# AVALON_hashunit_chip.net
KiCad netlist of a schematic drawn in Altium Designer
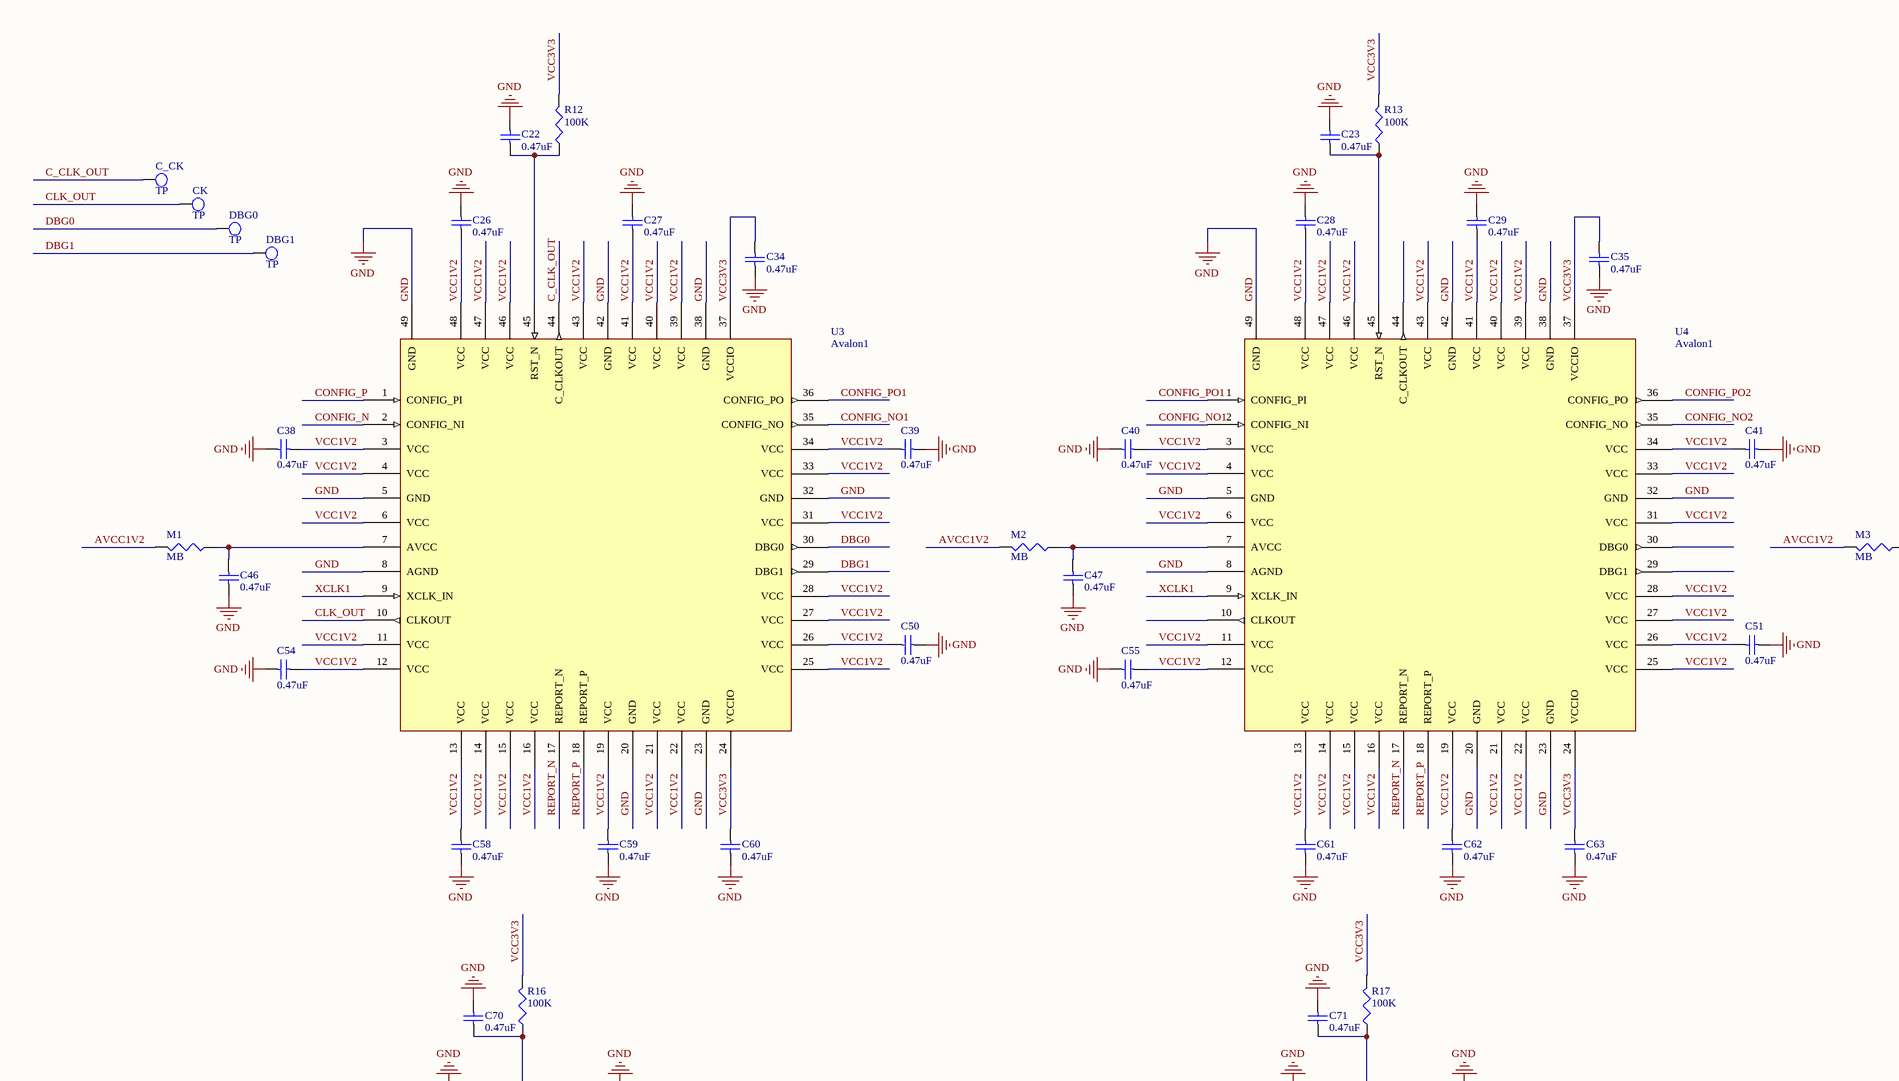
[diagram p0: AVALON_hashunit_chip.SchDoc, top left]
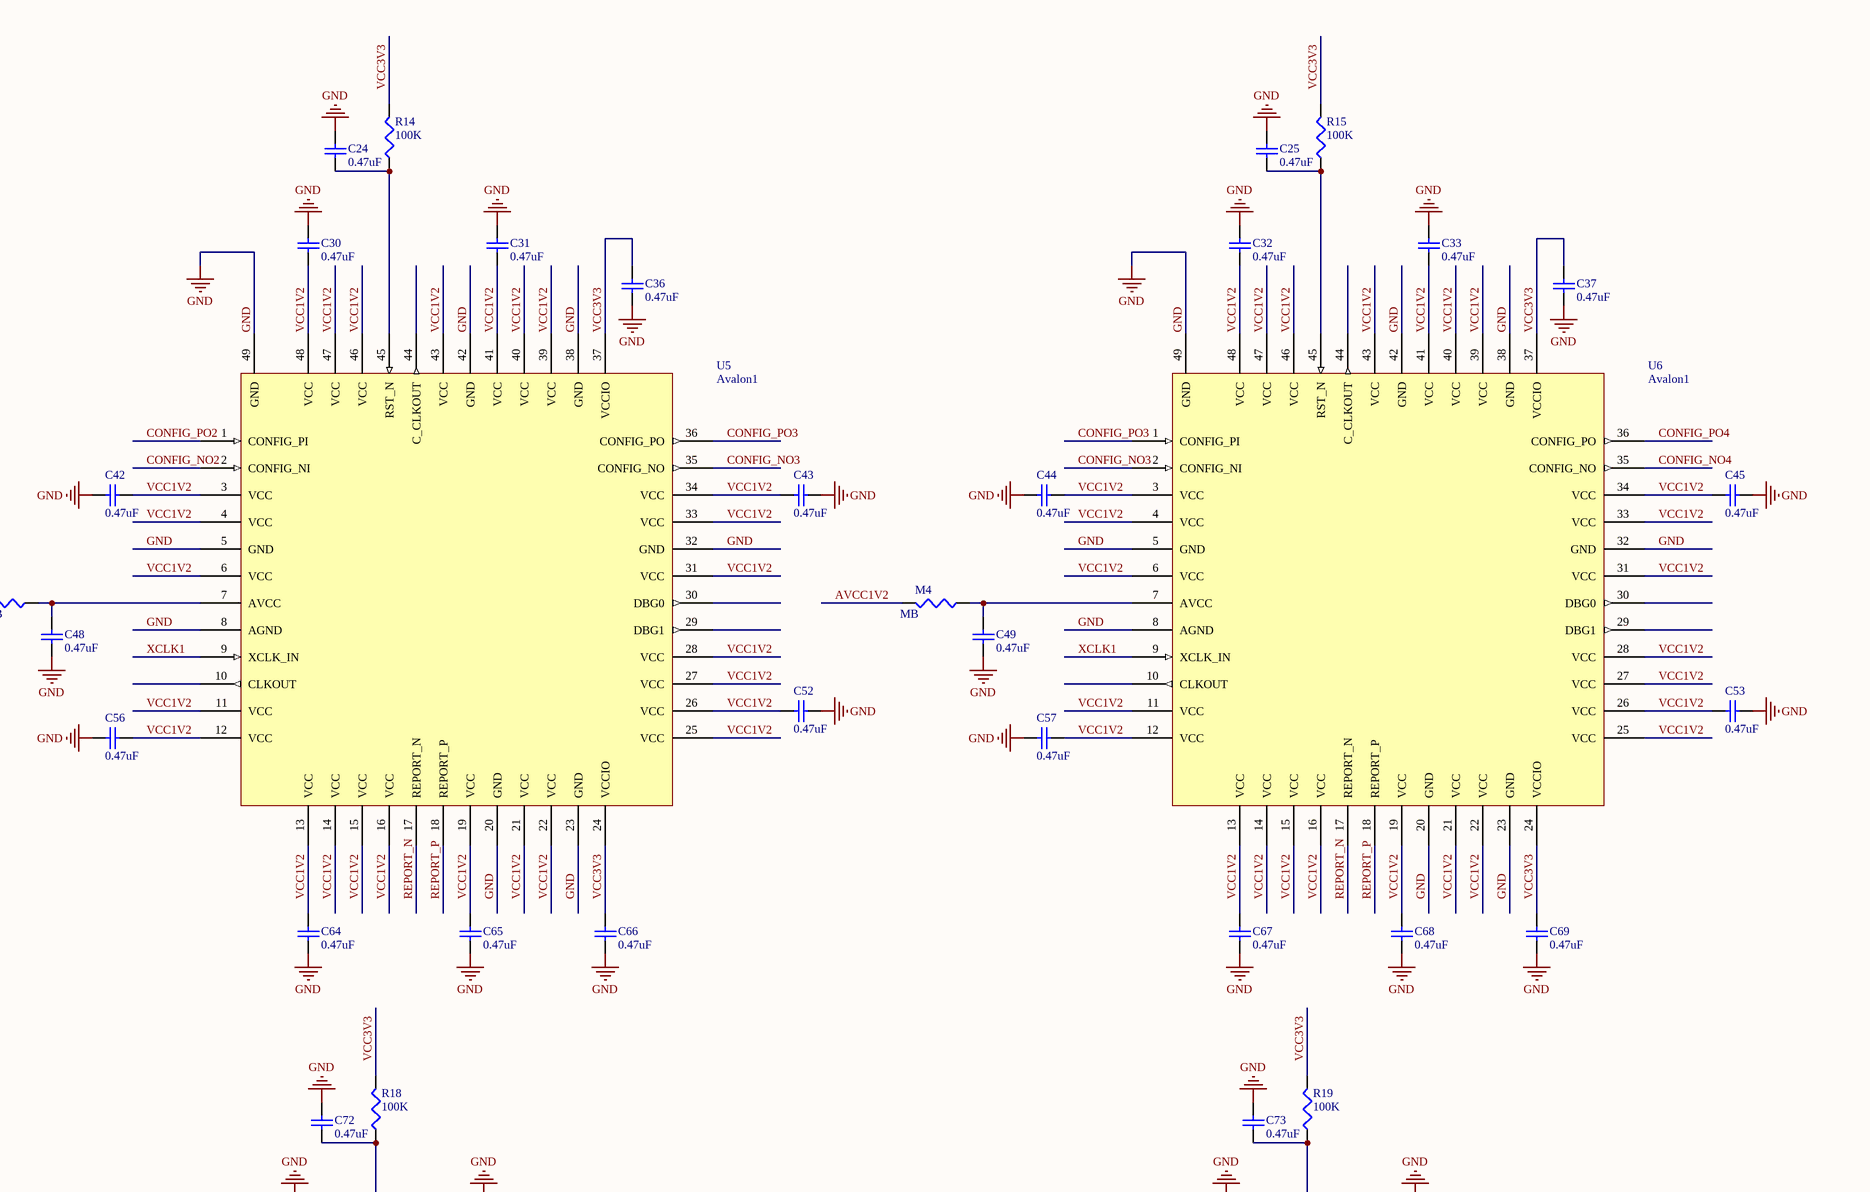
[diagram p1: AVALON_hashunit_chip.SchDoc, top right]
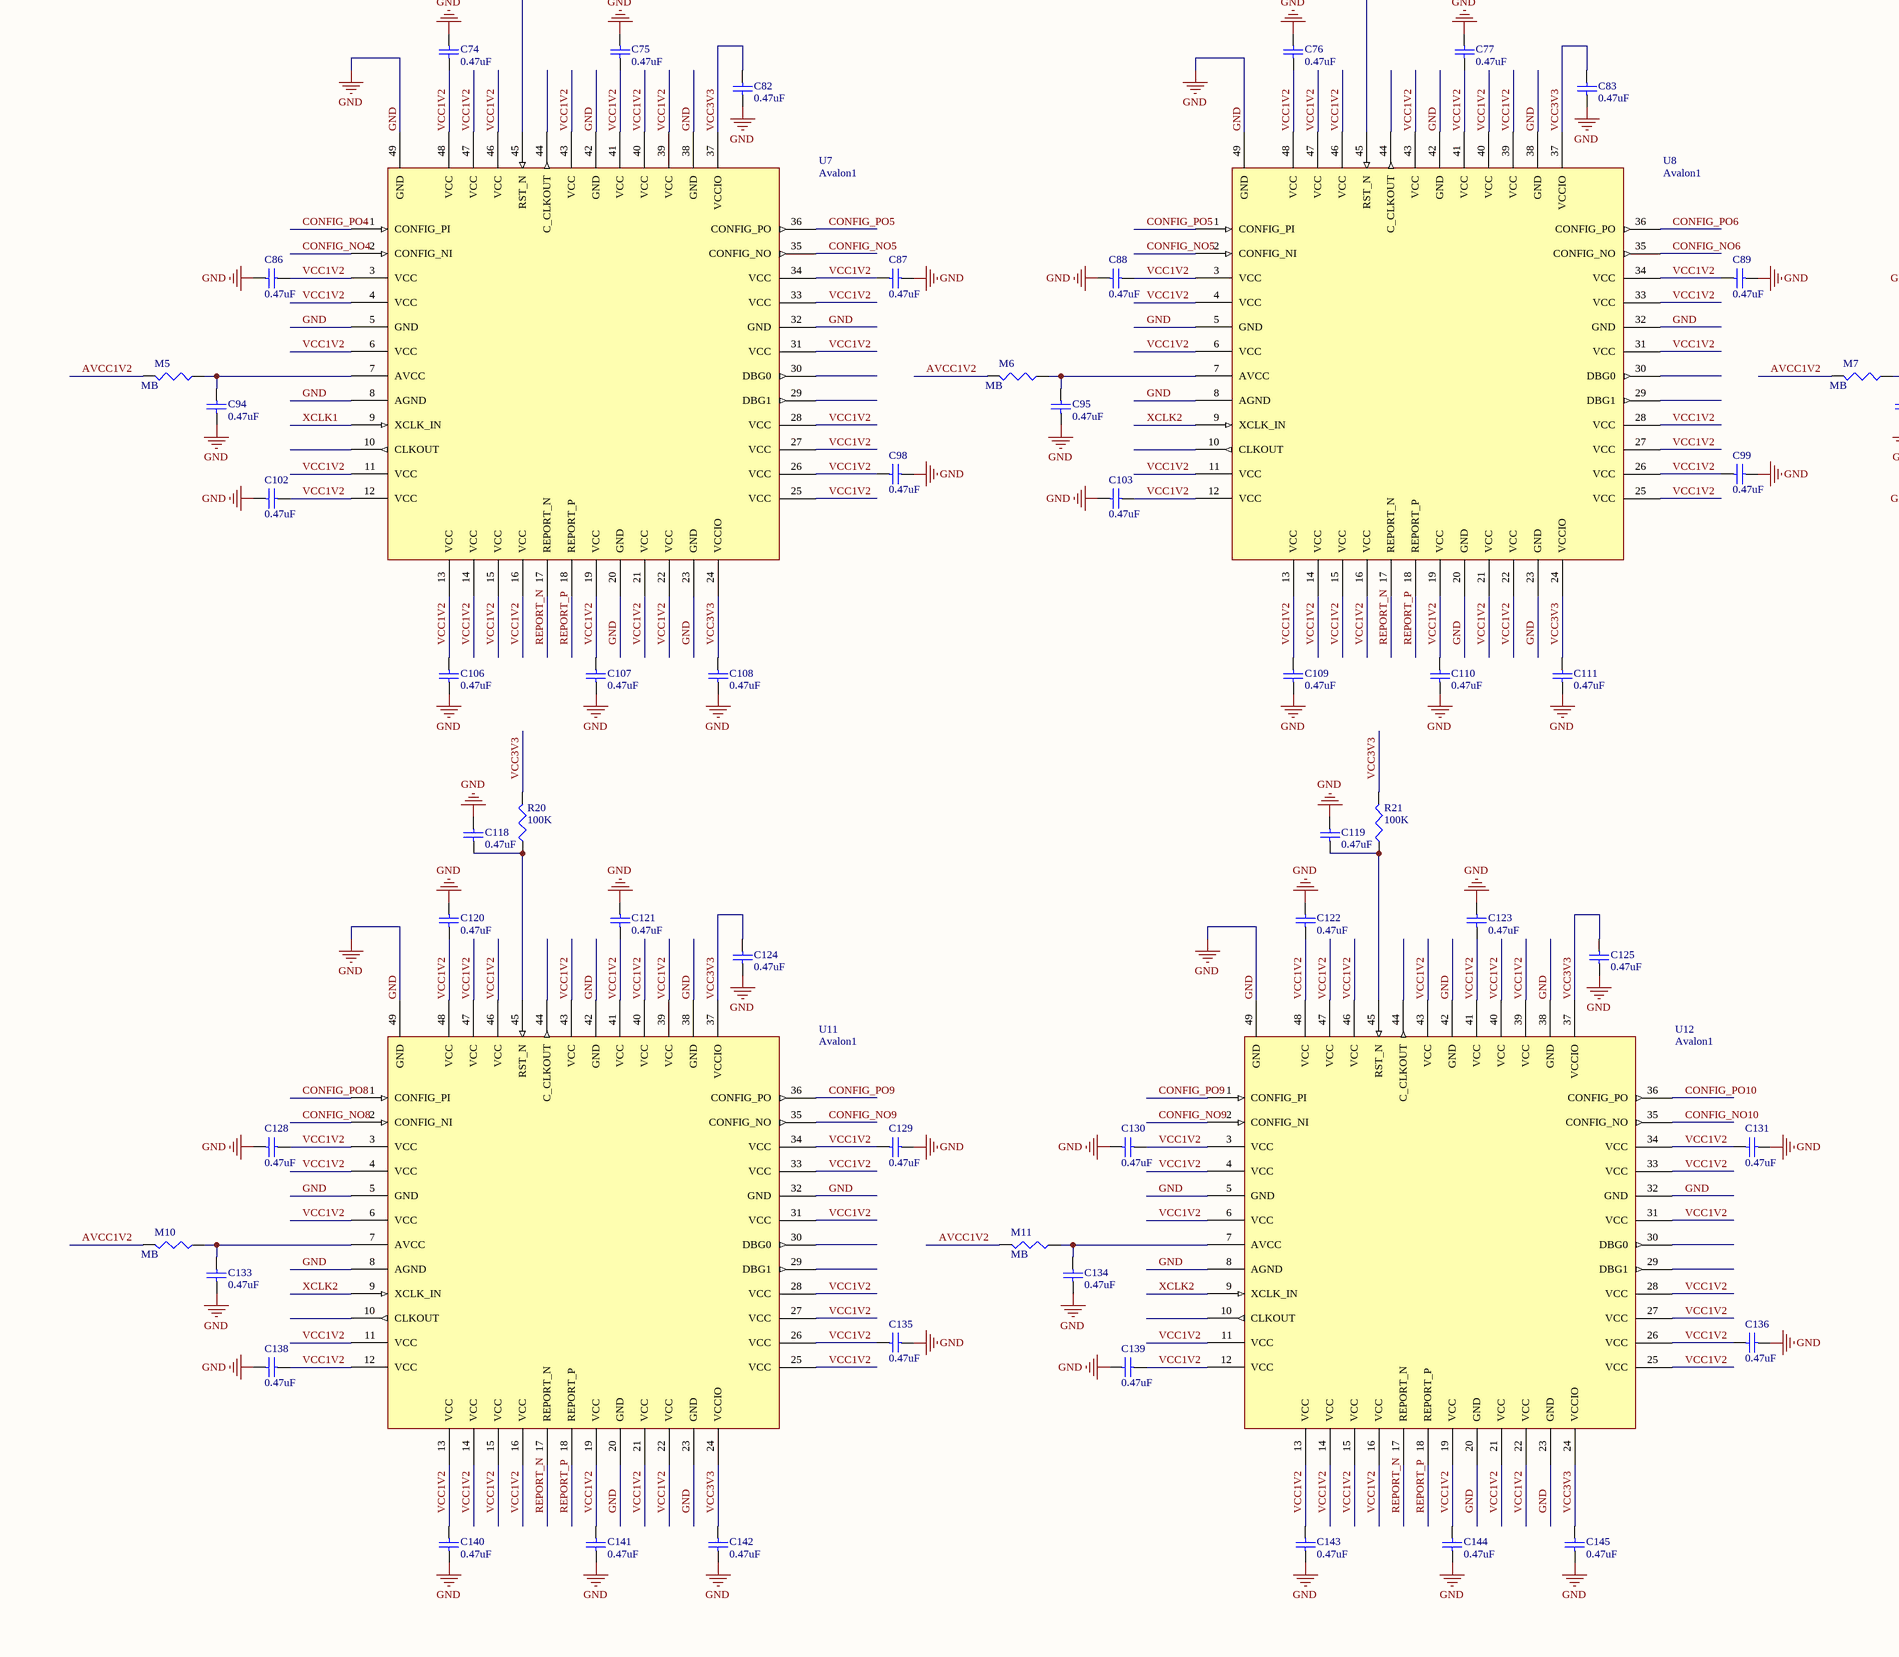
[diagram p2: AVALON_hashunit_chip.SchDoc, bottom left]
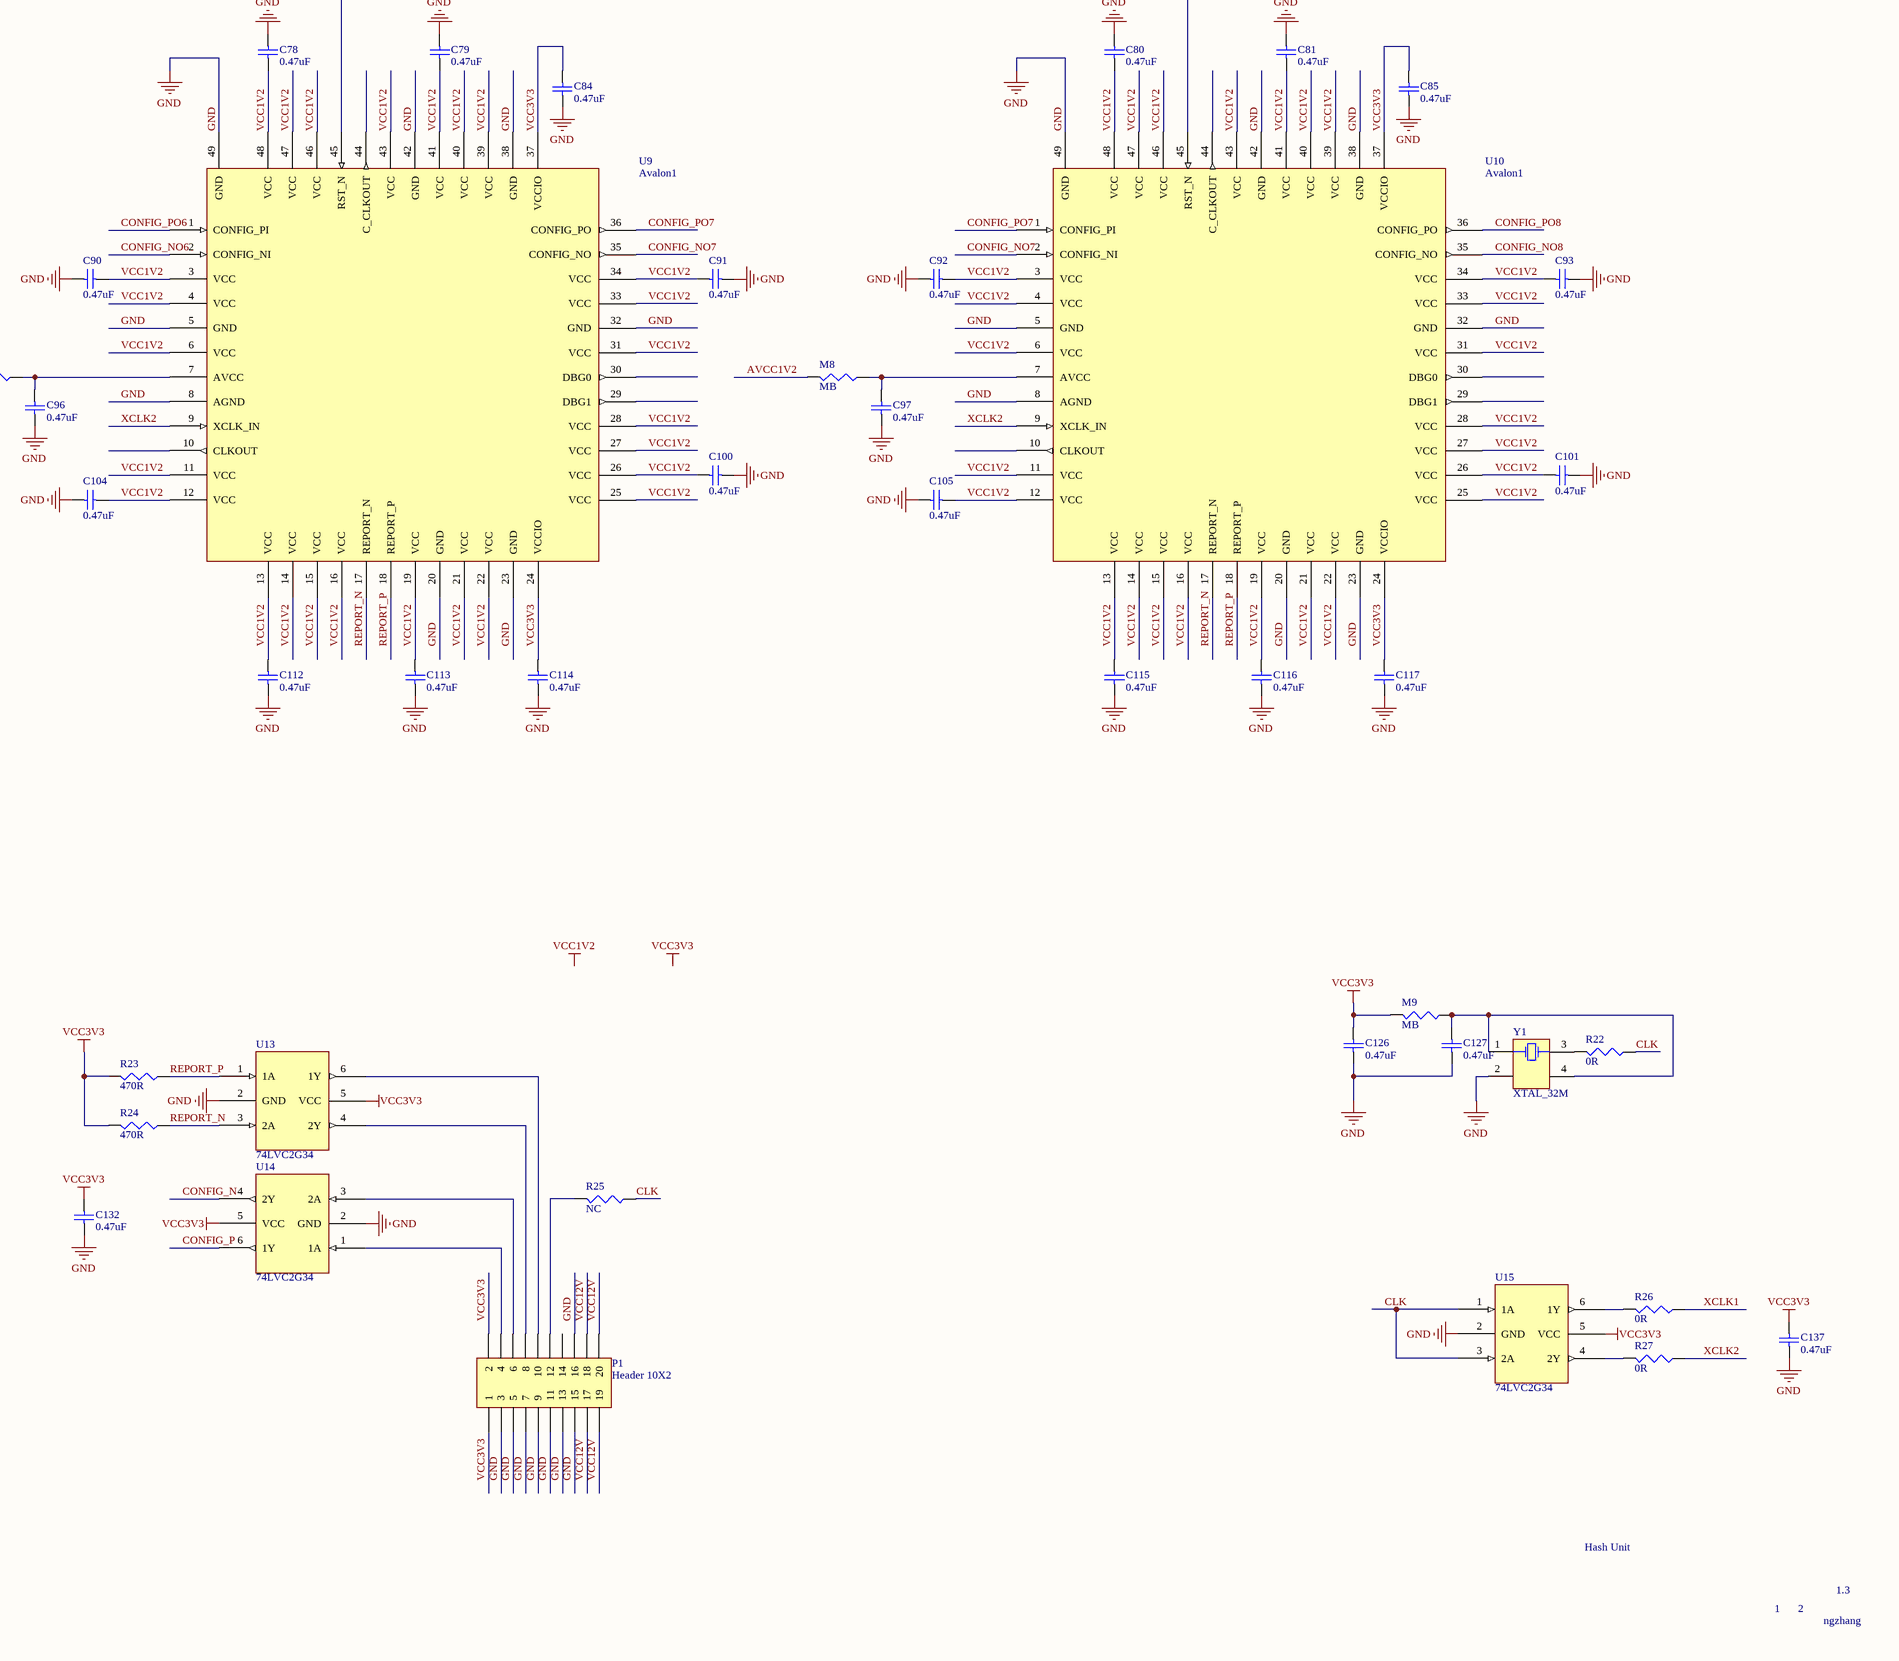
[diagram p3: AVALON_hashunit_chip.SchDoc, bottom right]

(export (version "E")
  (design (tool "Eeschema 10.0.6"))
  (components
    (comp (ref "C22")
      (value "0.47uF")
      (footprint "CAPC1005L")
      (description "Capacitor (Semiconductor SIM Model)")
      (fields (field (name "PUBLISHER") "Altium Limited"))
      (libsource (lib "Miscellaneous Devices") (part "Cap Semi"))
    )
    (comp (ref "C23")
      (value "0.47uF")
      (footprint "CAPC1005L")
      (description "Capacitor (Semiconductor SIM Model)")
      (fields (field (name "PUBLISHER") "Altium Limited"))
      (libsource (lib "Miscellaneous Devices") (part "Cap Semi"))
    )
    (comp (ref "C24")
      (value "0.47uF")
      (footprint "CAPC1005L")
      (description "Capacitor (Semiconductor SIM Model)")
      (fields (field (name "PUBLISHER") "Altium Limited"))
      (libsource (lib "Miscellaneous Devices") (part "Cap Semi"))
    )
    (comp (ref "C25")
      (value "0.47uF")
      (footprint "CAPC1005L")
      (description "Capacitor (Semiconductor SIM Model)")
      (fields (field (name "PUBLISHER") "Altium Limited"))
      (libsource (lib "Miscellaneous Devices") (part "Cap Semi"))
    )
    (comp (ref "C26")
      (value "0.47uF")
      (footprint "CAPC1005L")
      (description "Capacitor (Semiconductor SIM Model)")
      (fields (field (name "PUBLISHER") "Altium Limited"))
      (libsource (lib "Miscellaneous Devices") (part "Cap Semi"))
    )
    (comp (ref "C27")
      (value "0.47uF")
      (footprint "CAPC1005L")
      (description "Capacitor (Semiconductor SIM Model)")
      (fields (field (name "PUBLISHER") "Altium Limited"))
      (libsource (lib "Miscellaneous Devices") (part "Cap Semi"))
    )
    (comp (ref "C28")
      (value "0.47uF")
      (footprint "CAPC1005L")
      (description "Capacitor (Semiconductor SIM Model)")
      (fields (field (name "PUBLISHER") "Altium Limited"))
      (libsource (lib "Miscellaneous Devices") (part "Cap Semi"))
    )
    (comp (ref "C29")
      (value "0.47uF")
      (footprint "CAPC1005L")
      (description "Capacitor (Semiconductor SIM Model)")
      (fields (field (name "PUBLISHER") "Altium Limited"))
      (libsource (lib "Miscellaneous Devices") (part "Cap Semi"))
    )
    (comp (ref "C30")
      (value "0.47uF")
      (footprint "CAPC1005L")
      (description "Capacitor (Semiconductor SIM Model)")
      (fields (field (name "PUBLISHER") "Altium Limited"))
      (libsource (lib "Miscellaneous Devices") (part "Cap Semi"))
    )
    (comp (ref "C31")
      (value "0.47uF")
      (footprint "CAPC1005L")
      (description "Capacitor (Semiconductor SIM Model)")
      (fields (field (name "PUBLISHER") "Altium Limited"))
      (libsource (lib "Miscellaneous Devices") (part "Cap Semi"))
    )
    (comp (ref "C32")
      (value "0.47uF")
      (footprint "CAPC1005L")
      (description "Capacitor (Semiconductor SIM Model)")
      (fields (field (name "PUBLISHER") "Altium Limited"))
      (libsource (lib "Miscellaneous Devices") (part "Cap Semi"))
    )
    (comp (ref "C33")
      (value "0.47uF")
      (footprint "CAPC1005L")
      (description "Capacitor (Semiconductor SIM Model)")
      (fields (field (name "PUBLISHER") "Altium Limited"))
      (libsource (lib "Miscellaneous Devices") (part "Cap Semi"))
    )
    (comp (ref "C34")
      (value "0.47uF")
      (footprint "CAPC1005L")
      (description "Capacitor (Semiconductor SIM Model)")
      (fields (field (name "PUBLISHER") "Altium Limited"))
      (libsource (lib "Miscellaneous Devices") (part "Cap Semi"))
    )
    (comp (ref "C35")
      (value "0.47uF")
      (footprint "CAPC1005L")
      (description "Capacitor (Semiconductor SIM Model)")
      (fields (field (name "PUBLISHER") "Altium Limited"))
      (libsource (lib "Miscellaneous Devices") (part "Cap Semi"))
    )
    (comp (ref "C36")
      (value "0.47uF")
      (footprint "CAPC1005L")
      (description "Capacitor (Semiconductor SIM Model)")
      (fields (field (name "PUBLISHER") "Altium Limited"))
      (libsource (lib "Miscellaneous Devices") (part "Cap Semi"))
    )
    (comp (ref "C37")
      (value "0.47uF")
      (footprint "CAPC1005L")
      (description "Capacitor (Semiconductor SIM Model)")
      (fields (field (name "PUBLISHER") "Altium Limited"))
      (libsource (lib "Miscellaneous Devices") (part "Cap Semi"))
    )
    (comp (ref "C38")
      (value "0.47uF")
      (footprint "CAPC1005L")
      (description "Capacitor (Semiconductor SIM Model)")
      (fields (field (name "PUBLISHER") "Altium Limited"))
      (libsource (lib "Miscellaneous Devices") (part "Cap Semi"))
    )
    (comp (ref "C39")
      (value "0.47uF")
      (footprint "CAPC1005L")
      (description "Capacitor (Semiconductor SIM Model)")
      (fields (field (name "PUBLISHER") "Altium Limited"))
      (libsource (lib "Miscellaneous Devices") (part "Cap Semi"))
    )
    (comp (ref "C40")
      (value "0.47uF")
      (footprint "CAPC1005L")
      (description "Capacitor (Semiconductor SIM Model)")
      (fields (field (name "PUBLISHER") "Altium Limited"))
      (libsource (lib "Miscellaneous Devices") (part "Cap Semi"))
    )
    (comp (ref "C41")
      (value "0.47uF")
      (footprint "CAPC1005L")
      (description "Capacitor (Semiconductor SIM Model)")
      (fields (field (name "PUBLISHER") "Altium Limited"))
      (libsource (lib "Miscellaneous Devices") (part "Cap Semi"))
    )
    (comp (ref "C42")
      (value "0.47uF")
      (footprint "CAPC1005L")
      (description "Capacitor (Semiconductor SIM Model)")
      (fields (field (name "PUBLISHER") "Altium Limited"))
      (libsource (lib "Miscellaneous Devices") (part "Cap Semi"))
    )
    (comp (ref "C43")
      (value "0.47uF")
      (footprint "CAPC1005L")
      (description "Capacitor (Semiconductor SIM Model)")
      (fields (field (name "PUBLISHER") "Altium Limited"))
      (libsource (lib "Miscellaneous Devices") (part "Cap Semi"))
    )
    (comp (ref "C44")
      (value "0.47uF")
      (footprint "CAPC1005L")
      (description "Capacitor (Semiconductor SIM Model)")
      (fields (field (name "PUBLISHER") "Altium Limited"))
      (libsource (lib "Miscellaneous Devices") (part "Cap Semi"))
    )
    (comp (ref "C45")
      (value "0.47uF")
      (footprint "CAPC1005L")
      (description "Capacitor (Semiconductor SIM Model)")
      (fields (field (name "PUBLISHER") "Altium Limited"))
      (libsource (lib "Miscellaneous Devices") (part "Cap Semi"))
    )
    (comp (ref "C46")
      (value "0.47uF")
      (footprint "CAPC1005L")
      (description "Capacitor (Semiconductor SIM Model)")
      (fields (field (name "PUBLISHER") "Altium Limited"))
      (libsource (lib "Miscellaneous Devices") (part "Cap Semi"))
    )
    (comp (ref "C47")
      (value "0.47uF")
      (footprint "CAPC1005L")
      (description "Capacitor (Semiconductor SIM Model)")
      (fields (field (name "PUBLISHER") "Altium Limited"))
      (libsource (lib "Miscellaneous Devices") (part "Cap Semi"))
    )
    (comp (ref "C48")
      (value "0.47uF")
      (footprint "CAPC1005L")
      (description "Capacitor (Semiconductor SIM Model)")
      (fields (field (name "PUBLISHER") "Altium Limited"))
      (libsource (lib "Miscellaneous Devices") (part "Cap Semi"))
    )
    (comp (ref "C49")
      (value "0.47uF")
      (footprint "CAPC1005L")
      (description "Capacitor (Semiconductor SIM Model)")
      (fields (field (name "PUBLISHER") "Altium Limited"))
      (libsource (lib "Miscellaneous Devices") (part "Cap Semi"))
    )
    (comp (ref "C50")
      (value "0.47uF")
      (footprint "CAPC1005L")
      (description "Capacitor (Semiconductor SIM Model)")
      (fields (field (name "PUBLISHER") "Altium Limited"))
      (libsource (lib "Miscellaneous Devices") (part "Cap Semi"))
    )
    (comp (ref "C51")
      (value "0.47uF")
      (footprint "CAPC1005L")
      (description "Capacitor (Semiconductor SIM Model)")
      (fields (field (name "PUBLISHER") "Altium Limited"))
      (libsource (lib "Miscellaneous Devices") (part "Cap Semi"))
    )
    (comp (ref "C52")
      (value "0.47uF")
      (footprint "CAPC1005L")
      (description "Capacitor (Semiconductor SIM Model)")
      (fields (field (name "PUBLISHER") "Altium Limited"))
      (libsource (lib "Miscellaneous Devices") (part "Cap Semi"))
    )
    (comp (ref "C53")
      (value "0.47uF")
      (footprint "CAPC1005L")
      (description "Capacitor (Semiconductor SIM Model)")
      (fields (field (name "PUBLISHER") "Altium Limited"))
      (libsource (lib "Miscellaneous Devices") (part "Cap Semi"))
    )
    (comp (ref "C54")
      (value "0.47uF")
      (footprint "CAPC1005L")
      (description "Capacitor (Semiconductor SIM Model)")
      (fields (field (name "PUBLISHER") "Altium Limited"))
      (libsource (lib "Miscellaneous Devices") (part "Cap Semi"))
    )
    (comp (ref "C55")
      (value "0.47uF")
      (footprint "CAPC1005L")
      (description "Capacitor (Semiconductor SIM Model)")
      (fields (field (name "PUBLISHER") "Altium Limited"))
      (libsource (lib "Miscellaneous Devices") (part "Cap Semi"))
    )
    (comp (ref "C56")
      (value "0.47uF")
      (footprint "CAPC1005L")
      (description "Capacitor (Semiconductor SIM Model)")
      (fields (field (name "PUBLISHER") "Altium Limited"))
      (libsource (lib "Miscellaneous Devices") (part "Cap Semi"))
    )
    (comp (ref "C57")
      (value "0.47uF")
      (footprint "CAPC1005L")
      (description "Capacitor (Semiconductor SIM Model)")
      (fields (field (name "PUBLISHER") "Altium Limited"))
      (libsource (lib "Miscellaneous Devices") (part "Cap Semi"))
    )
    (comp (ref "C58")
      (value "0.47uF")
      (footprint "CAPC1005L")
      (description "Capacitor (Semiconductor SIM Model)")
      (fields (field (name "PUBLISHER") "Altium Limited"))
      (libsource (lib "Miscellaneous Devices") (part "Cap Semi"))
    )
    (comp (ref "C59")
      (value "0.47uF")
      (footprint "CAPC1005L")
      (description "Capacitor (Semiconductor SIM Model)")
      (fields (field (name "PUBLISHER") "Altium Limited"))
      (libsource (lib "Miscellaneous Devices") (part "Cap Semi"))
    )
    (comp (ref "C60")
      (value "0.47uF")
      (footprint "CAPC1005L")
      (description "Capacitor (Semiconductor SIM Model)")
      (fields (field (name "PUBLISHER") "Altium Limited"))
      (libsource (lib "Miscellaneous Devices") (part "Cap Semi"))
    )
    (comp (ref "C61")
      (value "0.47uF")
      (footprint "CAPC1005L")
      (description "Capacitor (Semiconductor SIM Model)")
      (fields (field (name "PUBLISHER") "Altium Limited"))
      (libsource (lib "Miscellaneous Devices") (part "Cap Semi"))
    )
    (comp (ref "C62")
      (value "0.47uF")
      (footprint "CAPC1005L")
      (description "Capacitor (Semiconductor SIM Model)")
      (fields (field (name "PUBLISHER") "Altium Limited"))
      (libsource (lib "Miscellaneous Devices") (part "Cap Semi"))
    )
    (comp (ref "C63")
      (value "0.47uF")
      (footprint "CAPC1005L")
      (description "Capacitor (Semiconductor SIM Model)")
      (fields (field (name "PUBLISHER") "Altium Limited"))
      (libsource (lib "Miscellaneous Devices") (part "Cap Semi"))
    )
    (comp (ref "C64")
      (value "0.47uF")
      (footprint "CAPC1005L")
      (description "Capacitor (Semiconductor SIM Model)")
      (fields (field (name "PUBLISHER") "Altium Limited"))
      (libsource (lib "Miscellaneous Devices") (part "Cap Semi"))
    )
    (comp (ref "C65")
      (value "0.47uF")
      (footprint "CAPC1005L")
      (description "Capacitor (Semiconductor SIM Model)")
      (fields (field (name "PUBLISHER") "Altium Limited"))
      (libsource (lib "Miscellaneous Devices") (part "Cap Semi"))
    )
    (comp (ref "C66")
      (value "0.47uF")
      (footprint "CAPC1005L")
      (description "Capacitor (Semiconductor SIM Model)")
      (fields (field (name "PUBLISHER") "Altium Limited"))
      (libsource (lib "Miscellaneous Devices") (part "Cap Semi"))
    )
    (comp (ref "C67")
      (value "0.47uF")
      (footprint "CAPC1005L")
      (description "Capacitor (Semiconductor SIM Model)")
      (fields (field (name "PUBLISHER") "Altium Limited"))
      (libsource (lib "Miscellaneous Devices") (part "Cap Semi"))
    )
    (comp (ref "C68")
      (value "0.47uF")
      (footprint "CAPC1005L")
      (description "Capacitor (Semiconductor SIM Model)")
      (fields (field (name "PUBLISHER") "Altium Limited"))
      (libsource (lib "Miscellaneous Devices") (part "Cap Semi"))
    )
    (comp (ref "C69")
      (value "0.47uF")
      (footprint "CAPC1005L")
      (description "Capacitor (Semiconductor SIM Model)")
      (fields (field (name "PUBLISHER") "Altium Limited"))
      (libsource (lib "Miscellaneous Devices") (part "Cap Semi"))
    )
    (comp (ref "C70")
      (value "0.47uF")
      (footprint "CAPC1005L")
      (description "Capacitor (Semiconductor SIM Model)")
      (fields (field (name "PUBLISHER") "Altium Limited"))
      (libsource (lib "Miscellaneous Devices") (part "Cap Semi"))
    )
    (comp (ref "C71")
      (value "0.47uF")
      (footprint "CAPC1005L")
      (description "Capacitor (Semiconductor SIM Model)")
      (fields (field (name "PUBLISHER") "Altium Limited"))
      (libsource (lib "Miscellaneous Devices") (part "Cap Semi"))
    )
    (comp (ref "C72")
      (value "0.47uF")
      (footprint "CAPC1005L")
      (description "Capacitor (Semiconductor SIM Model)")
      (fields (field (name "PUBLISHER") "Altium Limited"))
      (libsource (lib "Miscellaneous Devices") (part "Cap Semi"))
    )
    (comp (ref "C73")
      (value "0.47uF")
      (footprint "CAPC1005L")
      (description "Capacitor (Semiconductor SIM Model)")
      (fields (field (name "PUBLISHER") "Altium Limited"))
      (libsource (lib "Miscellaneous Devices") (part "Cap Semi"))
    )
    (comp (ref "C74")
      (value "0.47uF")
      (footprint "CAPC1005L")
      (description "Capacitor (Semiconductor SIM Model)")
      (fields (field (name "PUBLISHER") "Altium Limited"))
      (libsource (lib "Miscellaneous Devices") (part "Cap Semi"))
    )
    (comp (ref "C75")
      (value "0.47uF")
      (footprint "CAPC1005L")
      (description "Capacitor (Semiconductor SIM Model)")
      (fields (field (name "PUBLISHER") "Altium Limited"))
      (libsource (lib "Miscellaneous Devices") (part "Cap Semi"))
    )
    (comp (ref "C76")
      (value "0.47uF")
      (footprint "CAPC1005L")
      (description "Capacitor (Semiconductor SIM Model)")
      (fields (field (name "PUBLISHER") "Altium Limited"))
      (libsource (lib "Miscellaneous Devices") (part "Cap Semi"))
    )
    (comp (ref "C77")
      (value "0.47uF")
      (footprint "CAPC1005L")
      (description "Capacitor (Semiconductor SIM Model)")
      (fields (field (name "PUBLISHER") "Altium Limited"))
      (libsource (lib "Miscellaneous Devices") (part "Cap Semi"))
    )
    (comp (ref "C78")
      (value "0.47uF")
      (footprint "CAPC1005L")
      (description "Capacitor (Semiconductor SIM Model)")
      (fields (field (name "PUBLISHER") "Altium Limited"))
      (libsource (lib "Miscellaneous Devices") (part "Cap Semi"))
    )
    (comp (ref "C79")
      (value "0.47uF")
      (footprint "CAPC1005L")
      (description "Capacitor (Semiconductor SIM Model)")
      (fields (field (name "PUBLISHER") "Altium Limited"))
      (libsource (lib "Miscellaneous Devices") (part "Cap Semi"))
    )
    (comp (ref "C80")
      (value "0.47uF")
      (footprint "CAPC1005L")
      (description "Capacitor (Semiconductor SIM Model)")
      (fields (field (name "PUBLISHER") "Altium Limited"))
      (libsource (lib "Miscellaneous Devices") (part "Cap Semi"))
    )
    (comp (ref "C81")
      (value "0.47uF")
      (footprint "CAPC1005L")
      (description "Capacitor (Semiconductor SIM Model)")
      (fields (field (name "PUBLISHER") "Altium Limited"))
      (libsource (lib "Miscellaneous Devices") (part "Cap Semi"))
    )
    (comp (ref "C82")
      (value "0.47uF")
      (footprint "CAPC1005L")
      (description "Capacitor (Semiconductor SIM Model)")
      (fields (field (name "PUBLISHER") "Altium Limited"))
      (libsource (lib "Miscellaneous Devices") (part "Cap Semi"))
    )
    (comp (ref "C83")
      (value "0.47uF")
      (footprint "CAPC1005L")
      (description "Capacitor (Semiconductor SIM Model)")
      (fields (field (name "PUBLISHER") "Altium Limited"))
      (libsource (lib "Miscellaneous Devices") (part "Cap Semi"))
    )
    (comp (ref "C84")
      (value "0.47uF")
      (footprint "CAPC1005L")
      (description "Capacitor (Semiconductor SIM Model)")
      (fields (field (name "PUBLISHER") "Altium Limited"))
      (libsource (lib "Miscellaneous Devices") (part "Cap Semi"))
    )
    (comp (ref "C85")
      (value "0.47uF")
      (footprint "CAPC1005L")
      (description "Capacitor (Semiconductor SIM Model)")
      (fields (field (name "PUBLISHER") "Altium Limited"))
      (libsource (lib "Miscellaneous Devices") (part "Cap Semi"))
    )
    (comp (ref "C86")
      (value "0.47uF")
      (footprint "CAPC1005L")
      (description "Capacitor (Semiconductor SIM Model)")
      (fields (field (name "PUBLISHER") "Altium Limited"))
      (libsource (lib "Miscellaneous Devices") (part "Cap Semi"))
    )
    (comp (ref "C87")
      (value "0.47uF")
      (footprint "CAPC1005L")
      (description "Capacitor (Semiconductor SIM Model)")
      (fields (field (name "PUBLISHER") "Altium Limited"))
      (libsource (lib "Miscellaneous Devices") (part "Cap Semi"))
    )
    (comp (ref "C88")
      (value "0.47uF")
      (footprint "CAPC1005L")
      (description "Capacitor (Semiconductor SIM Model)")
      (fields (field (name "PUBLISHER") "Altium Limited"))
      (libsource (lib "Miscellaneous Devices") (part "Cap Semi"))
    )
    (comp (ref "C89")
      (value "0.47uF")
      (footprint "CAPC1005L")
      (description "Capacitor (Semiconductor SIM Model)")
      (fields (field (name "PUBLISHER") "Altium Limited"))
      (libsource (lib "Miscellaneous Devices") (part "Cap Semi"))
    )
    (comp (ref "C90")
      (value "0.47uF")
      (footprint "CAPC1005L")
      (description "Capacitor (Semiconductor SIM Model)")
      (fields (field (name "PUBLISHER") "Altium Limited"))
      (libsource (lib "Miscellaneous Devices") (part "Cap Semi"))
    )
    (comp (ref "C91")
      (value "0.47uF")
      (footprint "CAPC1005L")
      (description "Capacitor (Semiconductor SIM Model)")
      (fields (field (name "PUBLISHER") "Altium Limited"))
      (libsource (lib "Miscellaneous Devices") (part "Cap Semi"))
    )
    (comp (ref "C92")
      (value "0.47uF")
      (footprint "CAPC1005L")
      (description "Capacitor (Semiconductor SIM Model)")
      (fields (field (name "PUBLISHER") "Altium Limited"))
      (libsource (lib "Miscellaneous Devices") (part "Cap Semi"))
    )
    (comp (ref "C93")
      (value "0.47uF")
      (footprint "CAPC1005L")
      (description "Capacitor (Semiconductor SIM Model)")
      (fields (field (name "PUBLISHER") "Altium Limited"))
      (libsource (lib "Miscellaneous Devices") (part "Cap Semi"))
    )
    (comp (ref "C94")
      (value "0.47uF")
      (footprint "CAPC1005L")
      (description "Capacitor (Semiconductor SIM Model)")
      (fields (field (name "PUBLISHER") "Altium Limited"))
      (libsource (lib "Miscellaneous Devices") (part "Cap Semi"))
    )
    (comp (ref "C95")
      (value "0.47uF")
      (footprint "CAPC1005L")
      (description "Capacitor (Semiconductor SIM Model)")
      (fields (field (name "PUBLISHER") "Altium Limited"))
      (libsource (lib "Miscellaneous Devices") (part "Cap Semi"))
    )
    (comp (ref "C96")
      (value "0.47uF")
      (footprint "CAPC1005L")
      (description "Capacitor (Semiconductor SIM Model)")
      (fields (field (name "PUBLISHER") "Altium Limited"))
      (libsource (lib "Miscellaneous Devices") (part "Cap Semi"))
    )
    (comp (ref "C97")
      (value "0.47uF")
      (footprint "CAPC1005L")
      (description "Capacitor (Semiconductor SIM Model)")
      (fields (field (name "PUBLISHER") "Altium Limited"))
      (libsource (lib "Miscellaneous Devices") (part "Cap Semi"))
    )
    (comp (ref "C98")
      (value "0.47uF")
      (footprint "CAPC1005L")
      (description "Capacitor (Semiconductor SIM Model)")
      (fields (field (name "PUBLISHER") "Altium Limited"))
      (libsource (lib "Miscellaneous Devices") (part "Cap Semi"))
    )
    (comp (ref "C99")
      (value "0.47uF")
      (footprint "CAPC1005L")
      (description "Capacitor (Semiconductor SIM Model)")
      (fields (field (name "PUBLISHER") "Altium Limited"))
      (libsource (lib "Miscellaneous Devices") (part "Cap Semi"))
    )
    (comp (ref "C100")
      (value "0.47uF")
      (footprint "CAPC1005L")
      (description "Capacitor (Semiconductor SIM Model)")
      (fields (field (name "PUBLISHER") "Altium Limited"))
      (libsource (lib "Miscellaneous Devices") (part "Cap Semi"))
    )
    (comp (ref "C101")
      (value "0.47uF")
      (footprint "CAPC1005L")
      (description "Capacitor (Semiconductor SIM Model)")
      (fields (field (name "PUBLISHER") "Altium Limited"))
      (libsource (lib "Miscellaneous Devices") (part "Cap Semi"))
    )
    (comp (ref "C102")
      (value "0.47uF")
      (footprint "CAPC1005L")
      (description "Capacitor (Semiconductor SIM Model)")
      (fields (field (name "PUBLISHER") "Altium Limited"))
      (libsource (lib "Miscellaneous Devices") (part "Cap Semi"))
    )
    (comp (ref "C103")
      (value "0.47uF")
      (footprint "CAPC1005L")
      (description "Capacitor (Semiconductor SIM Model)")
      (fields (field (name "PUBLISHER") "Altium Limited"))
      (libsource (lib "Miscellaneous Devices") (part "Cap Semi"))
    )
    (comp (ref "C104")
      (value "0.47uF")
      (footprint "CAPC1005L")
      (description "Capacitor (Semiconductor SIM Model)")
      (fields (field (name "PUBLISHER") "Altium Limited"))
      (libsource (lib "Miscellaneous Devices") (part "Cap Semi"))
    )
    (comp (ref "C105")
      (value "0.47uF")
      (footprint "CAPC1005L")
      (description "Capacitor (Semiconductor SIM Model)")
      (fields (field (name "PUBLISHER") "Altium Limited"))
      (libsource (lib "Miscellaneous Devices") (part "Cap Semi"))
    )
    (comp (ref "C106")
      (value "0.47uF")
      (footprint "CAPC1005L")
      (description "Capacitor (Semiconductor SIM Model)")
      (fields (field (name "PUBLISHER") "Altium Limited"))
      (libsource (lib "Miscellaneous Devices") (part "Cap Semi"))
    )
    (comp (ref "C107")
      (value "0.47uF")
      (footprint "CAPC1005L")
      (description "Capacitor (Semiconductor SIM Model)")
      (fields (field (name "PUBLISHER") "Altium Limited"))
      (libsource (lib "Miscellaneous Devices") (part "Cap Semi"))
    )
    (comp (ref "C108")
      (value "0.47uF")
      (footprint "CAPC1005L")
      (description "Capacitor (Semiconductor SIM Model)")
      (fields (field (name "PUBLISHER") "Altium Limited"))
      (libsource (lib "Miscellaneous Devices") (part "Cap Semi"))
    )
    (comp (ref "C109")
      (value "0.47uF")
      (footprint "CAPC1005L")
      (description "Capacitor (Semiconductor SIM Model)")
      (fields (field (name "PUBLISHER") "Altium Limited"))
      (libsource (lib "Miscellaneous Devices") (part "Cap Semi"))
    )
    (comp (ref "C110")
      (value "0.47uF")
      (footprint "CAPC1005L")
      (description "Capacitor (Semiconductor SIM Model)")
      (fields (field (name "PUBLISHER") "Altium Limited"))
      (libsource (lib "Miscellaneous Devices") (part "Cap Semi"))
    )
    (comp (ref "C111")
      (value "0.47uF")
      (footprint "CAPC1005L")
      (description "Capacitor (Semiconductor SIM Model)")
      (fields (field (name "PUBLISHER") "Altium Limited"))
      (libsource (lib "Miscellaneous Devices") (part "Cap Semi"))
    )
    (comp (ref "C112")
      (value "0.47uF")
      (footprint "CAPC1005L")
      (description "Capacitor (Semiconductor SIM Model)")
      (fields (field (name "PUBLISHER") "Altium Limited"))
      (libsource (lib "Miscellaneous Devices") (part "Cap Semi"))
    )
    (comp (ref "C113")
      (value "0.47uF")
      (footprint "CAPC1005L")
      (description "Capacitor (Semiconductor SIM Model)")
      (fields (field (name "PUBLISHER") "Altium Limited"))
      (libsource (lib "Miscellaneous Devices") (part "Cap Semi"))
    )
    (comp (ref "C114")
      (value "0.47uF")
      (footprint "CAPC1005L")
      (description "Capacitor (Semiconductor SIM Model)")
      (fields (field (name "PUBLISHER") "Altium Limited"))
      (libsource (lib "Miscellaneous Devices") (part "Cap Semi"))
    )
    (comp (ref "C115")
      (value "0.47uF")
      (footprint "CAPC1005L")
      (description "Capacitor (Semiconductor SIM Model)")
      (fields (field (name "PUBLISHER") "Altium Limited"))
      (libsource (lib "Miscellaneous Devices") (part "Cap Semi"))
    )
    (comp (ref "C116")
      (value "0.47uF")
      (footprint "CAPC1005L")
      (description "Capacitor (Semiconductor SIM Model)")
      (fields (field (name "PUBLISHER") "Altium Limited"))
      (libsource (lib "Miscellaneous Devices") (part "Cap Semi"))
    )
    (comp (ref "C117")
      (value "0.47uF")
      (footprint "CAPC1005L")
      (description "Capacitor (Semiconductor SIM Model)")
      (fields (field (name "PUBLISHER") "Altium Limited"))
      (libsource (lib "Miscellaneous Devices") (part "Cap Semi"))
    )
    (comp (ref "C118")
      (value "0.47uF")
      (footprint "CAPC1005L")
      (description "Capacitor (Semiconductor SIM Model)")
      (fields (field (name "PUBLISHER") "Altium Limited"))
      (libsource (lib "Miscellaneous Devices") (part "Cap Semi"))
    )
    (comp (ref "C119")
      (value "0.47uF")
      (footprint "CAPC1005L")
      (description "Capacitor (Semiconductor SIM Model)")
      (fields (field (name "PUBLISHER") "Altium Limited"))
      (libsource (lib "Miscellaneous Devices") (part "Cap Semi"))
    )
    (comp (ref "C120")
      (value "0.47uF")
      (footprint "CAPC1005L")
      (description "Capacitor (Semiconductor SIM Model)")
      (fields (field (name "PUBLISHER") "Altium Limited"))
      (libsource (lib "Miscellaneous Devices") (part "Cap Semi"))
    )
    (comp (ref "C121")
      (value "0.47uF")
      (footprint "CAPC1005L")
      (description "Capacitor (Semiconductor SIM Model)")
      (fields (field (name "PUBLISHER") "Altium Limited"))
      (libsource (lib "Miscellaneous Devices") (part "Cap Semi"))
    )
    (comp (ref "C122")
      (value "0.47uF")
      (footprint "CAPC1005L")
      (description "Capacitor (Semiconductor SIM Model)")
      (fields (field (name "PUBLISHER") "Altium Limited"))
      (libsource (lib "Miscellaneous Devices") (part "Cap Semi"))
    )
    (comp (ref "C123")
      (value "0.47uF")
      (footprint "CAPC1005L")
      (description "Capacitor (Semiconductor SIM Model)")
      (fields (field (name "PUBLISHER") "Altium Limited"))
      (libsource (lib "Miscellaneous Devices") (part "Cap Semi"))
    )
    (comp (ref "C124")
      (value "0.47uF")
      (footprint "CAPC1005L")
      (description "Capacitor (Semiconductor SIM Model)")
      (fields (field (name "PUBLISHER") "Altium Limited"))
      (libsource (lib "Miscellaneous Devices") (part "Cap Semi"))
    )
    (comp (ref "C125")
      (value "0.47uF")
      (footprint "CAPC1005L")
      (description "Capacitor (Semiconductor SIM Model)")
      (fields (field (name "PUBLISHER") "Altium Limited"))
      (libsource (lib "Miscellaneous Devices") (part "Cap Semi"))
    )
    (comp (ref "C126")
      (value "0.47uF")
      (footprint "CAPC1005L")
      (description "Capacitor (Semiconductor SIM Model)")
      (fields (field (name "PUBLISHER") "Altium Limited"))
      (libsource (lib "Miscellaneous Devices") (part "Cap Semi"))
    )
    (comp (ref "C127")
      (value "0.47uF")
      (footprint "CAPC1005L")
      (description "Capacitor (Semiconductor SIM Model)")
      (fields (field (name "PUBLISHER") "Altium Limited"))
      (libsource (lib "Miscellaneous Devices") (part "Cap Semi"))
    )
    (comp (ref "C128")
      (value "0.47uF")
      (footprint "CAPC1005L")
      (description "Capacitor (Semiconductor SIM Model)")
      (fields (field (name "PUBLISHER") "Altium Limited"))
      (libsource (lib "Miscellaneous Devices") (part "Cap Semi"))
    )
    (comp (ref "C129")
      (value "0.47uF")
      (footprint "CAPC1005L")
      (description "Capacitor (Semiconductor SIM Model)")
      (fields (field (name "PUBLISHER") "Altium Limited"))
      (libsource (lib "Miscellaneous Devices") (part "Cap Semi"))
    )
    (comp (ref "C130")
      (value "0.47uF")
      (footprint "CAPC1005L")
      (description "Capacitor (Semiconductor SIM Model)")
      (fields (field (name "PUBLISHER") "Altium Limited"))
      (libsource (lib "Miscellaneous Devices") (part "Cap Semi"))
    )
    (comp (ref "C131")
      (value "0.47uF")
      (footprint "CAPC1005L")
      (description "Capacitor (Semiconductor SIM Model)")
      (fields (field (name "PUBLISHER") "Altium Limited"))
      (libsource (lib "Miscellaneous Devices") (part "Cap Semi"))
    )
    (comp (ref "C132")
      (value "0.47uF")
      (footprint "CAPC1005L")
      (description "Capacitor (Semiconductor SIM Model)")
      (fields (field (name "PUBLISHER") "Altium Limited"))
      (libsource (lib "Miscellaneous Devices") (part "Cap Semi"))
    )
    (comp (ref "C133")
      (value "0.47uF")
      (footprint "CAPC1005L")
      (description "Capacitor (Semiconductor SIM Model)")
      (fields (field (name "PUBLISHER") "Altium Limited"))
      (libsource (lib "Miscellaneous Devices") (part "Cap Semi"))
    )
    (comp (ref "C134")
      (value "0.47uF")
      (footprint "CAPC1005L")
      (description "Capacitor (Semiconductor SIM Model)")
      (fields (field (name "PUBLISHER") "Altium Limited"))
      (libsource (lib "Miscellaneous Devices") (part "Cap Semi"))
    )
    (comp (ref "C135")
      (value "0.47uF")
      (footprint "CAPC1005L")
      (description "Capacitor (Semiconductor SIM Model)")
      (fields (field (name "PUBLISHER") "Altium Limited"))
      (libsource (lib "Miscellaneous Devices") (part "Cap Semi"))
    )
    (comp (ref "C136")
      (value "0.47uF")
      (footprint "CAPC1005L")
      (description "Capacitor (Semiconductor SIM Model)")
      (fields (field (name "PUBLISHER") "Altium Limited"))
      (libsource (lib "Miscellaneous Devices") (part "Cap Semi"))
    )
    (comp (ref "C137")
      (value "0.47uF")
      (footprint "IPC-7352 Chip_Capacitor_L:CAPC1005L")
      (description "Capacitor (Semiconductor SIM Model)")
      (fields (field (name "PUBLISHER") "Altium Limited"))
      (libsource (lib "Miscellaneous Devices") (part "Cap Semi"))
    )
    (comp (ref "C138")
      (value "0.47uF")
      (footprint "CAPC1005L")
      (description "Capacitor (Semiconductor SIM Model)")
      (fields (field (name "PUBLISHER") "Altium Limited"))
      (libsource (lib "Miscellaneous Devices") (part "Cap Semi"))
    )
    (comp (ref "C139")
      (value "0.47uF")
      (footprint "CAPC1005L")
      (description "Capacitor (Semiconductor SIM Model)")
      (fields (field (name "PUBLISHER") "Altium Limited"))
      (libsource (lib "Miscellaneous Devices") (part "Cap Semi"))
    )
    (comp (ref "C140")
      (value "0.47uF")
      (footprint "CAPC1005L")
      (description "Capacitor (Semiconductor SIM Model)")
      (fields (field (name "PUBLISHER") "Altium Limited"))
      (libsource (lib "Miscellaneous Devices") (part "Cap Semi"))
    )
    (comp (ref "C141")
      (value "0.47uF")
      (footprint "CAPC1005L")
      (description "Capacitor (Semiconductor SIM Model)")
      (fields (field (name "PUBLISHER") "Altium Limited"))
      (libsource (lib "Miscellaneous Devices") (part "Cap Semi"))
    )
    (comp (ref "C142")
      (value "0.47uF")
      (footprint "CAPC1005L")
      (description "Capacitor (Semiconductor SIM Model)")
      (fields (field (name "PUBLISHER") "Altium Limited"))
      (libsource (lib "Miscellaneous Devices") (part "Cap Semi"))
    )
    (comp (ref "C143")
      (value "0.47uF")
      (footprint "CAPC1005L")
      (description "Capacitor (Semiconductor SIM Model)")
      (fields (field (name "PUBLISHER") "Altium Limited"))
      (libsource (lib "Miscellaneous Devices") (part "Cap Semi"))
    )
    (comp (ref "C144")
      (value "0.47uF")
      (footprint "CAPC1005L")
      (description "Capacitor (Semiconductor SIM Model)")
      (fields (field (name "PUBLISHER") "Altium Limited"))
      (libsource (lib "Miscellaneous Devices") (part "Cap Semi"))
    )
    (comp (ref "C145")
      (value "0.47uF")
      (footprint "CAPC1005L")
      (description "Capacitor (Semiconductor SIM Model)")
      (fields (field (name "PUBLISHER") "Altium Limited"))
      (libsource (lib "Miscellaneous Devices") (part "Cap Semi"))
    )
    (comp (ref "CK") (value "TP") (footprint "TP") (libsource (lib "S6") (part "TP")))
    (comp (ref "C_CK") (value "TP") (footprint "TP") (libsource (lib "S6") (part "TP")))
    (comp (ref "DBG0") (value "TP") (footprint "TP") (libsource (lib "S6") (part "TP")))
    (comp (ref "DBG1") (value "TP") (footprint "TP") (libsource (lib "S6") (part "TP")))
    (comp (ref "M1")
      (value "MB")
      (footprint "RESC1005L")
      (fields (field (name "PUBLISHER") "Altium Limited"))
      (libsource (lib "Miscellaneous Devices") (part "Res3"))
    )
    (comp (ref "M2")
      (value "MB")
      (footprint "RESC1005L")
      (fields (field (name "PUBLISHER") "Altium Limited"))
      (libsource (lib "Miscellaneous Devices") (part "Res3"))
    )
    (comp (ref "M3")
      (value "MB")
      (footprint "RESC1005L")
      (fields (field (name "PUBLISHER") "Altium Limited"))
      (libsource (lib "Miscellaneous Devices") (part "Res3"))
    )
    (comp (ref "M4")
      (value "MB")
      (footprint "RESC1005L")
      (fields (field (name "PUBLISHER") "Altium Limited"))
      (libsource (lib "Miscellaneous Devices") (part "Res3"))
    )
    (comp (ref "M5")
      (value "MB")
      (footprint "RESC1005L")
      (fields (field (name "PUBLISHER") "Altium Limited"))
      (libsource (lib "Miscellaneous Devices") (part "Res3"))
    )
    (comp (ref "M6")
      (value "MB")
      (footprint "RESC1005L")
      (fields (field (name "PUBLISHER") "Altium Limited"))
      (libsource (lib "Miscellaneous Devices") (part "Res3"))
    )
    (comp (ref "M7")
      (value "MB")
      (footprint "RESC1005L")
      (fields (field (name "PUBLISHER") "Altium Limited"))
      (libsource (lib "Miscellaneous Devices") (part "Res3"))
    )
    (comp (ref "M8")
      (value "MB")
      (footprint "RESC1005L")
      (fields (field (name "PUBLISHER") "Altium Limited"))
      (libsource (lib "Miscellaneous Devices") (part "Res3"))
    )
    (comp (ref "M9")
      (value "MB")
      (footprint "RESC1005L")
      (fields (field (name "PUBLISHER") "Altium Limited"))
      (libsource (lib "Miscellaneous Devices") (part "Res3"))
    )
    (comp (ref "M10")
      (value "MB")
      (footprint "RESC1005L")
      (fields (field (name "PUBLISHER") "Altium Limited"))
      (libsource (lib "Miscellaneous Devices") (part "Res3"))
    )
    (comp (ref "M11")
      (value "MB")
      (footprint "RESC1005L")
      (fields (field (name "PUBLISHER") "Altium Limited"))
      (libsource (lib "Miscellaneous Devices") (part "Res3"))
    )
    (comp (ref "P1")
      (value "Header 10X2")
      (footprint "20PINSMT")
      (description "Header, 10-Pin, Dual row")
      (fields (field (name "PUBLISHER") "Altium Limited"))
      (libsource (lib "Miscellaneous Connectors") (part "Header 10X2"))
    )
    (comp (ref "R12")
      (value "100K")
      (footprint "RESC1005L")
      (description "Resistor")
      (fields (field (name "PUBLISHER") "Altium Limited"))
      (libsource (lib "Miscellaneous Devices") (part "Res3"))
    )
    (comp (ref "R13")
      (value "100K")
      (footprint "RESC1005L")
      (description "Resistor")
      (fields (field (name "PUBLISHER") "Altium Limited"))
      (libsource (lib "Miscellaneous Devices") (part "Res3"))
    )
    (comp (ref "R14")
      (value "100K")
      (footprint "RESC1005L")
      (description "Resistor")
      (fields (field (name "PUBLISHER") "Altium Limited"))
      (libsource (lib "Miscellaneous Devices") (part "Res3"))
    )
    (comp (ref "R15")
      (value "100K")
      (footprint "RESC1005L")
      (description "Resistor")
      (fields (field (name "PUBLISHER") "Altium Limited"))
      (libsource (lib "Miscellaneous Devices") (part "Res3"))
    )
    (comp (ref "R16")
      (value "100K")
      (footprint "RESC1005L")
      (description "Resistor")
      (fields (field (name "PUBLISHER") "Altium Limited"))
      (libsource (lib "Miscellaneous Devices") (part "Res3"))
    )
    (comp (ref "R17")
      (value "100K")
      (footprint "RESC1005L")
      (description "Resistor")
      (fields (field (name "PUBLISHER") "Altium Limited"))
      (libsource (lib "Miscellaneous Devices") (part "Res3"))
    )
    (comp (ref "R18")
      (value "100K")
      (footprint "RESC1005L")
      (description "Resistor")
      (fields (field (name "PUBLISHER") "Altium Limited"))
      (libsource (lib "Miscellaneous Devices") (part "Res3"))
    )
    (comp (ref "R19")
      (value "100K")
      (footprint "RESC1005L")
      (description "Resistor")
      (fields (field (name "PUBLISHER") "Altium Limited"))
      (libsource (lib "Miscellaneous Devices") (part "Res3"))
    )
    (comp (ref "R20")
      (value "100K")
      (footprint "RESC1005L")
      (description "Resistor")
      (fields (field (name "PUBLISHER") "Altium Limited"))
      (libsource (lib "Miscellaneous Devices") (part "Res3"))
    )
    (comp (ref "R21")
      (value "100K")
      (footprint "RESC1005L")
      (description "Resistor")
      (fields (field (name "PUBLISHER") "Altium Limited"))
      (libsource (lib "Miscellaneous Devices") (part "Res3"))
    )
    (comp (ref "R22")
      (value "0R")
      (footprint "RESC1005L")
      (description "Resistor")
      (fields (field (name "PUBLISHER") "Altium Limited"))
      (libsource (lib "Miscellaneous Devices") (part "Res3"))
    )
    (comp (ref "R23")
      (value "470R")
      (footprint "RESC1005L")
      (description "Resistor")
      (fields (field (name "PUBLISHER") "Altium Limited"))
      (libsource (lib "Miscellaneous Devices") (part "Res3"))
    )
    (comp (ref "R24")
      (value "470R")
      (footprint "RESC1005L")
      (description "Resistor")
      (fields (field (name "PUBLISHER") "Altium Limited"))
      (libsource (lib "Miscellaneous Devices") (part "Res3"))
    )
    (comp (ref "R25")
      (value "NC")
      (footprint "RESC1005L")
      (description "Resistor")
      (fields (field (name "PUBLISHER") "Altium Limited"))
      (libsource (lib "Miscellaneous Devices") (part "Res3"))
    )
    (comp (ref "R26")
      (value "0R")
      (footprint "RESC1005L")
      (description "Resistor")
      (fields (field (name "PUBLISHER") "Altium Limited"))
      (libsource (lib "Miscellaneous Devices") (part "Res3"))
    )
    (comp (ref "R27")
      (value "0R")
      (footprint "RESC1005L")
      (description "Resistor")
      (fields (field (name "PUBLISHER") "Altium Limited"))
      (libsource (lib "Miscellaneous Devices") (part "Res3"))
    )
    (comp (ref "U3") (value "Avalon1") (footprint "QFN48NT7A") (libsource (lib "AVALON.") (part "Avalon1")))
    (comp (ref "U4") (value "Avalon1") (footprint "QFN48NT7A") (libsource (lib "AVALON.") (part "Avalon1")))
    (comp (ref "U5") (value "Avalon1") (footprint "QFN48NT7A") (libsource (lib "AVALON.") (part "Avalon1")))
    (comp (ref "U6") (value "Avalon1") (footprint "QFN48NT7A") (libsource (lib "AVALON.") (part "Avalon1")))
    (comp (ref "U7") (value "Avalon1") (footprint "QFN48NT7A") (libsource (lib "AVALON.") (part "Avalon1")))
    (comp (ref "U8") (value "Avalon1") (footprint "QFN48NT7A") (libsource (lib "AVALON.") (part "Avalon1")))
    (comp (ref "U9") (value "Avalon1") (footprint "QFN48NT7A") (libsource (lib "AVALON.") (part "Avalon1")))
    (comp (ref "U10") (value "Avalon1") (footprint "QFN48NT7A") (libsource (lib "AVALON.") (part "Avalon1")))
    (comp (ref "U11") (value "Avalon1") (footprint "QFN48NT7A") (libsource (lib "AVALON.") (part "Avalon1")))
    (comp (ref "U12") (value "Avalon1") (footprint "QFN48NT7A") (libsource (lib "AVALON.") (part "Avalon1")))
    (comp (ref "U13") (value "74LVC2G34") (footprint "SOT363_L") (libsource (lib "") (part "74LVC2G34_1")))
    (comp (ref "U14") (value "74LVC2G34") (footprint "SOT363_L") (libsource (lib "S6_2") (part "74LVC2G34")))
    (comp (ref "U15") (value "74LVC2G34") (footprint "SOT363_L") (libsource (lib "") (part "74LVC2G34_1")))
    (comp (ref "Y1")
      (value "XTAL_32M")
      (footprint "SMX2")
      (description "Surface Mount Quartz Crystal")
      (fields (field (name "PUBLISHER") "Altium Limited"))
      (libsource (lib "C-MAC Crystal Oscillator") (part "2SMX"))
    )
  )
  (nets
    (net (code "1") (name "/AVCC1V2") (class "Default")
      (node (ref "M1") (pin "2") (pinfunction "2_2") (pintype "passive"))
      (node (ref "M10") (pin "2") (pinfunction "2_2") (pintype "passive"))
      (node (ref "M11") (pin "2") (pinfunction "2_2") (pintype "passive"))
      (node (ref "M2") (pin "2") (pinfunction "2_2") (pintype "passive"))
      (node (ref "M3") (pin "2") (pinfunction "2_2") (pintype "passive"))
      (node (ref "M4") (pin "2") (pinfunction "2_2") (pintype "passive"))
      (node (ref "M5") (pin "2") (pinfunction "2_2") (pintype "passive"))
      (node (ref "M6") (pin "2") (pinfunction "2_2") (pintype "passive"))
      (node (ref "M7") (pin "2") (pinfunction "2_2") (pintype "passive"))
      (node (ref "M8") (pin "2") (pinfunction "2_2") (pintype "passive"))
    )
    (net (code "2") (name "/CLK") (class "Default")
      (node (ref "R22") (pin "1") (pinfunction "1_1") (pintype "passive"))
      (node (ref "R25") (pin "1") (pinfunction "1_1") (pintype "passive"))
      (node (ref "U15") (pin "1") (pinfunction "1A_1") (pintype "input"))
      (node (ref "U15") (pin "3") (pinfunction "2A_3") (pintype "input"))
    )
    (net (code "3") (name "/CLK_OUT") (class "Default")
      (node (ref "CK") (pin "1") (pinfunction "TP_1") (pintype "passive"))
      (node (ref "U3") (pin "10") (pinfunction "CLKOUT_10") (pintype "output"))
    )
    (net (code "4") (name "/CONFIG_N") (class "Default")
      (node (ref "U14") (pin "4") (pinfunction "2Y_4") (pintype "output"))
      (node (ref "U3") (pin "2") (pinfunction "CONFIG_NI_2") (pintype "input"))
    )
    (net (code "5") (name "/CONFIG_NO1") (class "Default")
      (node (ref "U3") (pin "35") (pinfunction "CONFIG_NO_35") (pintype "output"))
      (node (ref "U4") (pin "2") (pinfunction "CONFIG_NI_2") (pintype "input"))
    )
    (net (code "6") (name "/CONFIG_NO2") (class "Default")
      (node (ref "U4") (pin "35") (pinfunction "CONFIG_NO_35") (pintype "output"))
      (node (ref "U5") (pin "2") (pinfunction "CONFIG_NI_2") (pintype "input"))
    )
    (net (code "7") (name "/CONFIG_NO3") (class "Default")
      (node (ref "U5") (pin "35") (pinfunction "CONFIG_NO_35") (pintype "output"))
      (node (ref "U6") (pin "2") (pinfunction "CONFIG_NI_2") (pintype "input"))
    )
    (net (code "8") (name "/CONFIG_NO4") (class "Default")
      (node (ref "U6") (pin "35") (pinfunction "CONFIG_NO_35") (pintype "output"))
      (node (ref "U7") (pin "2") (pinfunction "CONFIG_NI_2") (pintype "input"))
    )
    (net (code "9") (name "/CONFIG_NO5") (class "Default")
      (node (ref "U7") (pin "35") (pinfunction "CONFIG_NO_35") (pintype "output"))
      (node (ref "U8") (pin "2") (pinfunction "CONFIG_NI_2") (pintype "input"))
    )
    (net (code "10") (name "/CONFIG_NO6") (class "Default")
      (node (ref "U8") (pin "35") (pinfunction "CONFIG_NO_35") (pintype "output"))
      (node (ref "U9") (pin "2") (pinfunction "CONFIG_NI_2") (pintype "input"))
    )
    (net (code "11") (name "/CONFIG_NO7") (class "Default")
      (node (ref "U10") (pin "2") (pinfunction "CONFIG_NI_2") (pintype "input"))
      (node (ref "U9") (pin "35") (pinfunction "CONFIG_NO_35") (pintype "output"))
    )
    (net (code "12") (name "/CONFIG_NO8") (class "Default")
      (node (ref "U10") (pin "35") (pinfunction "CONFIG_NO_35") (pintype "output"))
      (node (ref "U11") (pin "2") (pinfunction "CONFIG_NI_2") (pintype "input"))
    )
    (net (code "13") (name "/CONFIG_NO9") (class "Default")
      (node (ref "U11") (pin "35") (pinfunction "CONFIG_NO_35") (pintype "output"))
      (node (ref "U12") (pin "2") (pinfunction "CONFIG_NI_2") (pintype "input"))
    )
    (net (code "14") (name "/CONFIG_NO10") (class "Default")
      (node (ref "U12") (pin "35") (pinfunction "CONFIG_NO_35") (pintype "output"))
    )
    (net (code "15") (name "/CONFIG_P") (class "Default")
      (node (ref "U14") (pin "6") (pinfunction "1Y_6") (pintype "output"))
      (node (ref "U3") (pin "1") (pinfunction "CONFIG_PI_1") (pintype "input"))
    )
    (net (code "16") (name "/CONFIG_PO1") (class "Default")
      (node (ref "U3") (pin "36") (pinfunction "CONFIG_PO_36") (pintype "output"))
      (node (ref "U4") (pin "1") (pinfunction "CONFIG_PI_1") (pintype "input"))
    )
    (net (code "17") (name "/CONFIG_PO2") (class "Default")
      (node (ref "U4") (pin "36") (pinfunction "CONFIG_PO_36") (pintype "output"))
      (node (ref "U5") (pin "1") (pinfunction "CONFIG_PI_1") (pintype "input"))
    )
    (net (code "18") (name "/CONFIG_PO3") (class "Default")
      (node (ref "U5") (pin "36") (pinfunction "CONFIG_PO_36") (pintype "output"))
      (node (ref "U6") (pin "1") (pinfunction "CONFIG_PI_1") (pintype "input"))
    )
    (net (code "19") (name "/CONFIG_PO4") (class "Default")
      (node (ref "U6") (pin "36") (pinfunction "CONFIG_PO_36") (pintype "output"))
      (node (ref "U7") (pin "1") (pinfunction "CONFIG_PI_1") (pintype "input"))
    )
    (net (code "20") (name "/CONFIG_PO5") (class "Default")
      (node (ref "U7") (pin "36") (pinfunction "CONFIG_PO_36") (pintype "output"))
      (node (ref "U8") (pin "1") (pinfunction "CONFIG_PI_1") (pintype "input"))
    )
    (net (code "21") (name "/CONFIG_PO6") (class "Default")
      (node (ref "U8") (pin "36") (pinfunction "CONFIG_PO_36") (pintype "output"))
      (node (ref "U9") (pin "1") (pinfunction "CONFIG_PI_1") (pintype "input"))
    )
    (net (code "22") (name "/CONFIG_PO7") (class "Default")
      (node (ref "U10") (pin "1") (pinfunction "CONFIG_PI_1") (pintype "input"))
      (node (ref "U9") (pin "36") (pinfunction "CONFIG_PO_36") (pintype "output"))
    )
    (net (code "23") (name "/CONFIG_PO8") (class "Default")
      (node (ref "U10") (pin "36") (pinfunction "CONFIG_PO_36") (pintype "output"))
      (node (ref "U11") (pin "1") (pinfunction "CONFIG_PI_1") (pintype "input"))
    )
    (net (code "24") (name "/CONFIG_PO9") (class "Default")
      (node (ref "U11") (pin "36") (pinfunction "CONFIG_PO_36") (pintype "output"))
      (node (ref "U12") (pin "1") (pinfunction "CONFIG_PI_1") (pintype "input"))
    )
    (net (code "25") (name "/CONFIG_PO10") (class "Default")
      (node (ref "U12") (pin "36") (pinfunction "CONFIG_PO_36") (pintype "output"))
    )
    (net (code "26") (name "/C_CLK_OUT") (class "Default")
      (node (ref "C_CK") (pin "1") (pinfunction "TP_1") (pintype "passive"))
      (node (ref "U3") (pin "44") (pinfunction "C_CLKOUT_44") (pintype "output"))
    )
    (net (code "27") (name "/DBG0") (class "Default")
      (node (ref "DBG0") (pin "1") (pinfunction "TP_1") (pintype "passive"))
      (node (ref "U3") (pin "30") (pinfunction "DBG0_30") (pintype "output"))
    )
    (net (code "28") (name "/DBG1") (class "Default")
      (node (ref "DBG1") (pin "1") (pinfunction "TP_1") (pintype "passive"))
      (node (ref "U3") (pin "29") (pinfunction "DBG1_29") (pintype "output"))
    )
    (net (code "29") (name "/REPORT_N") (class "Default")
      (node (ref "R24") (pin "1") (pinfunction "1_1") (pintype "passive"))
      (node (ref "U10") (pin "17") (pinfunction "REPORT_N_17") (pintype "open_collector"))
      (node (ref "U11") (pin "17") (pinfunction "REPORT_N_17") (pintype "open_collector"))
      (node (ref "U12") (pin "17") (pinfunction "REPORT_N_17") (pintype "open_collector"))
      (node (ref "U13") (pin "3") (pinfunction "2A_3") (pintype "input"))
      (node (ref "U3") (pin "17") (pinfunction "REPORT_N_17") (pintype "open_collector"))
      (node (ref "U4") (pin "17") (pinfunction "REPORT_N_17") (pintype "open_collector"))
      (node (ref "U5") (pin "17") (pinfunction "REPORT_N_17") (pintype "open_collector"))
      (node (ref "U6") (pin "17") (pinfunction "REPORT_N_17") (pintype "open_collector"))
      (node (ref "U7") (pin "17") (pinfunction "REPORT_N_17") (pintype "open_collector"))
      (node (ref "U8") (pin "17") (pinfunction "REPORT_N_17") (pintype "open_collector"))
      (node (ref "U9") (pin "17") (pinfunction "REPORT_N_17") (pintype "open_collector"))
    )
    (net (code "30") (name "/REPORT_P") (class "Default")
      (node (ref "R23") (pin "1") (pinfunction "1_1") (pintype "passive"))
      (node (ref "U10") (pin "18") (pinfunction "REPORT_P_18") (pintype "open_collector"))
      (node (ref "U11") (pin "18") (pinfunction "REPORT_P_18") (pintype "open_collector"))
      (node (ref "U12") (pin "18") (pinfunction "REPORT_P_18") (pintype "open_collector"))
      (node (ref "U13") (pin "1") (pinfunction "1A_1") (pintype "input"))
      (node (ref "U3") (pin "18") (pinfunction "REPORT_P_18") (pintype "open_collector"))
      (node (ref "U4") (pin "18") (pinfunction "REPORT_P_18") (pintype "open_collector"))
      (node (ref "U5") (pin "18") (pinfunction "REPORT_P_18") (pintype "open_collector"))
      (node (ref "U6") (pin "18") (pinfunction "REPORT_P_18") (pintype "open_collector"))
      (node (ref "U7") (pin "18") (pinfunction "REPORT_P_18") (pintype "open_collector"))
      (node (ref "U8") (pin "18") (pinfunction "REPORT_P_18") (pintype "open_collector"))
      (node (ref "U9") (pin "18") (pinfunction "REPORT_P_18") (pintype "open_collector"))
    )
    (net (code "31") (name "/VCC12V") (class "Default")
      (node (ref "P1") (pin "17") (pinfunction "17_17") (pintype "passive"))
      (node (ref "P1") (pin "18") (pinfunction "18_18") (pintype "passive"))
      (node (ref "P1") (pin "19") (pinfunction "19_19") (pintype "passive"))
      (node (ref "P1") (pin "20") (pinfunction "20_20") (pintype "passive"))
    )
    (net (code "32") (name "/XCLK1") (class "Default")
      (node (ref "R26") (pin "1") (pinfunction "1_1") (pintype "passive"))
      (node (ref "U3") (pin "9") (pinfunction "XCLK_IN_9") (pintype "input"))
      (node (ref "U4") (pin "9") (pinfunction "XCLK_IN_9") (pintype "input"))
      (node (ref "U5") (pin "9") (pinfunction "XCLK_IN_9") (pintype "input"))
      (node (ref "U6") (pin "9") (pinfunction "XCLK_IN_9") (pintype "input"))
      (node (ref "U7") (pin "9") (pinfunction "XCLK_IN_9") (pintype "input"))
    )
    (net (code "33") (name "/XCLK2") (class "Default")
      (node (ref "R27") (pin "1") (pinfunction "1_1") (pintype "passive"))
      (node (ref "U10") (pin "9") (pinfunction "XCLK_IN_9") (pintype "input"))
      (node (ref "U11") (pin "9") (pinfunction "XCLK_IN_9") (pintype "input"))
      (node (ref "U12") (pin "9") (pinfunction "XCLK_IN_9") (pintype "input"))
      (node (ref "U8") (pin "9") (pinfunction "XCLK_IN_9") (pintype "input"))
      (node (ref "U9") (pin "9") (pinfunction "XCLK_IN_9") (pintype "input"))
    )
    (net (code "34") (name "GND") (class "Default")
      (node (ref "C100") (pin "1") (pinfunction "1_1") (pintype "passive"))
      (node (ref "C101") (pin "1") (pinfunction "1_1") (pintype "passive"))
      (node (ref "C102") (pin "2") (pinfunction "2_2") (pintype "passive"))
      (node (ref "C103") (pin "2") (pinfunction "2_2") (pintype "passive"))
      (node (ref "C104") (pin "2") (pinfunction "2_2") (pintype "passive"))
      (node (ref "C105") (pin "2") (pinfunction "2_2") (pintype "passive"))
      (node (ref "C106") (pin "1") (pinfunction "1_1") (pintype "passive"))
      (node (ref "C107") (pin "1") (pinfunction "1_1") (pintype "passive"))
      (node (ref "C108") (pin "1") (pinfunction "1_1") (pintype "passive"))
      (node (ref "C109") (pin "1") (pinfunction "1_1") (pintype "passive"))
      (node (ref "C110") (pin "1") (pinfunction "1_1") (pintype "passive"))
      (node (ref "C111") (pin "1") (pinfunction "1_1") (pintype "passive"))
      (node (ref "C112") (pin "1") (pinfunction "1_1") (pintype "passive"))
      (node (ref "C113") (pin "1") (pinfunction "1_1") (pintype "passive"))
      (node (ref "C114") (pin "1") (pinfunction "1_1") (pintype "passive"))
      (node (ref "C115") (pin "1") (pinfunction "1_1") (pintype "passive"))
      (node (ref "C116") (pin "1") (pinfunction "1_1") (pintype "passive"))
      (node (ref "C117") (pin "1") (pinfunction "1_1") (pintype "passive"))
      (node (ref "C118") (pin "2") (pinfunction "2_2") (pintype "passive"))
      (node (ref "C119") (pin "2") (pinfunction "2_2") (pintype "passive"))
      (node (ref "C120") (pin "2") (pinfunction "2_2") (pintype "passive"))
      (node (ref "C121") (pin "1") (pinfunction "1_1") (pintype "passive"))
      (node (ref "C122") (pin "2") (pinfunction "2_2") (pintype "passive"))
      (node (ref "C123") (pin "1") (pinfunction "1_1") (pintype "passive"))
      (node (ref "C124") (pin "1") (pinfunction "1_1") (pintype "passive"))
      (node (ref "C125") (pin "1") (pinfunction "1_1") (pintype "passive"))
      (node (ref "C126") (pin "1") (pinfunction "1_1") (pintype "passive"))
      (node (ref "C127") (pin "1") (pinfunction "1_1") (pintype "passive"))
      (node (ref "C128") (pin "2") (pinfunction "2_2") (pintype "passive"))
      (node (ref "C129") (pin "1") (pinfunction "1_1") (pintype "passive"))
      (node (ref "C130") (pin "2") (pinfunction "2_2") (pintype "passive"))
      (node (ref "C131") (pin "1") (pinfunction "1_1") (pintype "passive"))
      (node (ref "C132") (pin "2") (pinfunction "2_2") (pintype "passive"))
      (node (ref "C133") (pin "2") (pinfunction "2_2") (pintype "passive"))
      (node (ref "C134") (pin "2") (pinfunction "2_2") (pintype "passive"))
      (node (ref "C135") (pin "1") (pinfunction "1_1") (pintype "passive"))
      (node (ref "C136") (pin "1") (pinfunction "1_1") (pintype "passive"))
      (node (ref "C137") (pin "2") (pinfunction "2_2") (pintype "passive"))
      (node (ref "C138") (pin "2") (pinfunction "2_2") (pintype "passive"))
      (node (ref "C139") (pin "2") (pinfunction "2_2") (pintype "passive"))
      (node (ref "C140") (pin "1") (pinfunction "1_1") (pintype "passive"))
      (node (ref "C141") (pin "1") (pinfunction "1_1") (pintype "passive"))
      (node (ref "C142") (pin "1") (pinfunction "1_1") (pintype "passive"))
      (node (ref "C143") (pin "1") (pinfunction "1_1") (pintype "passive"))
      (node (ref "C144") (pin "1") (pinfunction "1_1") (pintype "passive"))
      (node (ref "C145") (pin "1") (pinfunction "1_1") (pintype "passive"))
      (node (ref "C22") (pin "2") (pinfunction "2_2") (pintype "passive"))
      (node (ref "C23") (pin "2") (pinfunction "2_2") (pintype "passive"))
      (node (ref "C24") (pin "2") (pinfunction "2_2") (pintype "passive"))
      (node (ref "C25") (pin "2") (pinfunction "2_2") (pintype "passive"))
      (node (ref "C26") (pin "2") (pinfunction "2_2") (pintype "passive"))
      (node (ref "C27") (pin "1") (pinfunction "1_1") (pintype "passive"))
      (node (ref "C28") (pin "2") (pinfunction "2_2") (pintype "passive"))
      (node (ref "C29") (pin "1") (pinfunction "1_1") (pintype "passive"))
      (node (ref "C30") (pin "2") (pinfunction "2_2") (pintype "passive"))
      (node (ref "C31") (pin "1") (pinfunction "1_1") (pintype "passive"))
      (node (ref "C32") (pin "2") (pinfunction "2_2") (pintype "passive"))
      (node (ref "C33") (pin "1") (pinfunction "1_1") (pintype "passive"))
      (node (ref "C34") (pin "1") (pinfunction "1_1") (pintype "passive"))
      (node (ref "C35") (pin "1") (pinfunction "1_1") (pintype "passive"))
      (node (ref "C36") (pin "1") (pinfunction "1_1") (pintype "passive"))
      (node (ref "C37") (pin "1") (pinfunction "1_1") (pintype "passive"))
      (node (ref "C38") (pin "2") (pinfunction "2_2") (pintype "passive"))
      (node (ref "C39") (pin "1") (pinfunction "1_1") (pintype "passive"))
      (node (ref "C40") (pin "2") (pinfunction "2_2") (pintype "passive"))
      (node (ref "C41") (pin "1") (pinfunction "1_1") (pintype "passive"))
      (node (ref "C42") (pin "2") (pinfunction "2_2") (pintype "passive"))
      (node (ref "C43") (pin "1") (pinfunction "1_1") (pintype "passive"))
      (node (ref "C44") (pin "2") (pinfunction "2_2") (pintype "passive"))
      (node (ref "C45") (pin "1") (pinfunction "1_1") (pintype "passive"))
      (node (ref "C46") (pin "2") (pinfunction "2_2") (pintype "passive"))
      (node (ref "C47") (pin "2") (pinfunction "2_2") (pintype "passive"))
      (node (ref "C48") (pin "2") (pinfunction "2_2") (pintype "passive"))
      (node (ref "C49") (pin "2") (pinfunction "2_2") (pintype "passive"))
      (node (ref "C50") (pin "1") (pinfunction "1_1") (pintype "passive"))
      (node (ref "C51") (pin "1") (pinfunction "1_1") (pintype "passive"))
      (node (ref "C52") (pin "1") (pinfunction "1_1") (pintype "passive"))
      (node (ref "C53") (pin "1") (pinfunction "1_1") (pintype "passive"))
      (node (ref "C54") (pin "2") (pinfunction "2_2") (pintype "passive"))
      (node (ref "C55") (pin "2") (pinfunction "2_2") (pintype "passive"))
      (node (ref "C56") (pin "2") (pinfunction "2_2") (pintype "passive"))
      (node (ref "C57") (pin "2") (pinfunction "2_2") (pintype "passive"))
      (node (ref "C58") (pin "1") (pinfunction "1_1") (pintype "passive"))
      (node (ref "C59") (pin "1") (pinfunction "1_1") (pintype "passive"))
      (node (ref "C60") (pin "1") (pinfunction "1_1") (pintype "passive"))
      (node (ref "C61") (pin "1") (pinfunction "1_1") (pintype "passive"))
      (node (ref "C62") (pin "1") (pinfunction "1_1") (pintype "passive"))
      (node (ref "C63") (pin "1") (pinfunction "1_1") (pintype "passive"))
      (node (ref "C64") (pin "1") (pinfunction "1_1") (pintype "passive"))
      (node (ref "C65") (pin "1") (pinfunction "1_1") (pintype "passive"))
      (node (ref "C66") (pin "1") (pinfunction "1_1") (pintype "passive"))
      (node (ref "C67") (pin "1") (pinfunction "1_1") (pintype "passive"))
      (node (ref "C68") (pin "1") (pinfunction "1_1") (pintype "passive"))
      (node (ref "C69") (pin "1") (pinfunction "1_1") (pintype "passive"))
      (node (ref "C70") (pin "2") (pinfunction "2_2") (pintype "passive"))
      (node (ref "C71") (pin "2") (pinfunction "2_2") (pintype "passive"))
      (node (ref "C72") (pin "2") (pinfunction "2_2") (pintype "passive"))
      (node (ref "C73") (pin "2") (pinfunction "2_2") (pintype "passive"))
      (node (ref "C74") (pin "2") (pinfunction "2_2") (pintype "passive"))
      (node (ref "C75") (pin "1") (pinfunction "1_1") (pintype "passive"))
      (node (ref "C76") (pin "2") (pinfunction "2_2") (pintype "passive"))
      (node (ref "C77") (pin "1") (pinfunction "1_1") (pintype "passive"))
      (node (ref "C78") (pin "2") (pinfunction "2_2") (pintype "passive"))
      (node (ref "C79") (pin "1") (pinfunction "1_1") (pintype "passive"))
      (node (ref "C80") (pin "2") (pinfunction "2_2") (pintype "passive"))
      (node (ref "C81") (pin "1") (pinfunction "1_1") (pintype "passive"))
      (node (ref "C82") (pin "1") (pinfunction "1_1") (pintype "passive"))
      (node (ref "C83") (pin "1") (pinfunction "1_1") (pintype "passive"))
      (node (ref "C84") (pin "1") (pinfunction "1_1") (pintype "passive"))
      (node (ref "C85") (pin "1") (pinfunction "1_1") (pintype "passive"))
      (node (ref "C86") (pin "2") (pinfunction "2_2") (pintype "passive"))
      (node (ref "C87") (pin "1") (pinfunction "1_1") (pintype "passive"))
      (node (ref "C88") (pin "2") (pinfunction "2_2") (pintype "passive"))
      (node (ref "C89") (pin "1") (pinfunction "1_1") (pintype "passive"))
      (node (ref "C90") (pin "2") (pinfunction "2_2") (pintype "passive"))
      (node (ref "C91") (pin "1") (pinfunction "1_1") (pintype "passive"))
      (node (ref "C92") (pin "2") (pinfunction "2_2") (pintype "passive"))
      (node (ref "C93") (pin "1") (pinfunction "1_1") (pintype "passive"))
      (node (ref "C94") (pin "2") (pinfunction "2_2") (pintype "passive"))
      (node (ref "C95") (pin "2") (pinfunction "2_2") (pintype "passive"))
      (node (ref "C96") (pin "2") (pinfunction "2_2") (pintype "passive"))
      (node (ref "C97") (pin "2") (pinfunction "2_2") (pintype "passive"))
      (node (ref "C98") (pin "1") (pinfunction "1_1") (pintype "passive"))
      (node (ref "C99") (pin "1") (pinfunction "1_1") (pintype "passive"))
      (node (ref "P1") (pin "11") (pinfunction "11_11") (pintype "passive"))
      (node (ref "P1") (pin "13") (pinfunction "13_13") (pintype "passive"))
      (node (ref "P1") (pin "15") (pinfunction "15_15") (pintype "passive"))
      (node (ref "P1") (pin "16") (pinfunction "16_16") (pintype "passive"))
      (node (ref "P1") (pin "3") (pinfunction "3_3") (pintype "passive"))
      (node (ref "P1") (pin "5") (pinfunction "5_5") (pintype "passive"))
      (node (ref "P1") (pin "7") (pinfunction "7_7") (pintype "passive"))
      (node (ref "P1") (pin "9") (pinfunction "9_9") (pintype "passive"))
      (node (ref "U10") (pin "20") (pinfunction "GND_20") (pintype "power_in"))
      (node (ref "U10") (pin "23") (pinfunction "GND_23") (pintype "power_in"))
      (node (ref "U10") (pin "32") (pinfunction "GND_32") (pintype "power_in"))
      (node (ref "U10") (pin "38") (pinfunction "GND_38") (pintype "power_in"))
      (node (ref "U10") (pin "42") (pinfunction "GND_42") (pintype "power_in"))
      (node (ref "U10") (pin "49") (pinfunction "GND_49") (pintype "power_in"))
      (node (ref "U10") (pin "5") (pinfunction "GND_5") (pintype "power_in"))
      (node (ref "U10") (pin "8") (pinfunction "AGND_8") (pintype "power_in"))
      (node (ref "U11") (pin "20") (pinfunction "GND_20") (pintype "power_in"))
      (node (ref "U11") (pin "23") (pinfunction "GND_23") (pintype "power_in"))
      (node (ref "U11") (pin "32") (pinfunction "GND_32") (pintype "power_in"))
      (node (ref "U11") (pin "38") (pinfunction "GND_38") (pintype "power_in"))
      (node (ref "U11") (pin "42") (pinfunction "GND_42") (pintype "power_in"))
      (node (ref "U11") (pin "49") (pinfunction "GND_49") (pintype "power_in"))
      (node (ref "U11") (pin "5") (pinfunction "GND_5") (pintype "power_in"))
      (node (ref "U11") (pin "8") (pinfunction "AGND_8") (pintype "power_in"))
      (node (ref "U12") (pin "20") (pinfunction "GND_20") (pintype "power_in"))
      (node (ref "U12") (pin "23") (pinfunction "GND_23") (pintype "power_in"))
      (node (ref "U12") (pin "32") (pinfunction "GND_32") (pintype "power_in"))
      (node (ref "U12") (pin "38") (pinfunction "GND_38") (pintype "power_in"))
      (node (ref "U12") (pin "42") (pinfunction "GND_42") (pintype "power_in"))
      (node (ref "U12") (pin "49") (pinfunction "GND_49") (pintype "power_in"))
      (node (ref "U12") (pin "5") (pinfunction "GND_5") (pintype "power_in"))
      (node (ref "U12") (pin "8") (pinfunction "AGND_8") (pintype "power_in"))
      (node (ref "U13") (pin "2") (pinfunction "GND_2") (pintype "power_in"))
      (node (ref "U14") (pin "2") (pinfunction "GND_2") (pintype "power_in"))
      (node (ref "U15") (pin "2") (pinfunction "GND_2") (pintype "power_in"))
      (node (ref "U3") (pin "20") (pinfunction "GND_20") (pintype "power_in"))
      (node (ref "U3") (pin "23") (pinfunction "GND_23") (pintype "power_in"))
      (node (ref "U3") (pin "32") (pinfunction "GND_32") (pintype "power_in"))
      (node (ref "U3") (pin "38") (pinfunction "GND_38") (pintype "power_in"))
      (node (ref "U3") (pin "42") (pinfunction "GND_42") (pintype "power_in"))
      (node (ref "U3") (pin "49") (pinfunction "GND_49") (pintype "power_in"))
      (node (ref "U3") (pin "5") (pinfunction "GND_5") (pintype "power_in"))
      (node (ref "U3") (pin "8") (pinfunction "AGND_8") (pintype "power_in"))
      (node (ref "U4") (pin "20") (pinfunction "GND_20") (pintype "power_in"))
      (node (ref "U4") (pin "23") (pinfunction "GND_23") (pintype "power_in"))
      (node (ref "U4") (pin "32") (pinfunction "GND_32") (pintype "power_in"))
      (node (ref "U4") (pin "38") (pinfunction "GND_38") (pintype "power_in"))
      (node (ref "U4") (pin "42") (pinfunction "GND_42") (pintype "power_in"))
      (node (ref "U4") (pin "49") (pinfunction "GND_49") (pintype "power_in"))
      (node (ref "U4") (pin "5") (pinfunction "GND_5") (pintype "power_in"))
      (node (ref "U4") (pin "8") (pinfunction "AGND_8") (pintype "power_in"))
      (node (ref "U5") (pin "20") (pinfunction "GND_20") (pintype "power_in"))
      (node (ref "U5") (pin "23") (pinfunction "GND_23") (pintype "power_in"))
      (node (ref "U5") (pin "32") (pinfunction "GND_32") (pintype "power_in"))
      (node (ref "U5") (pin "38") (pinfunction "GND_38") (pintype "power_in"))
      (node (ref "U5") (pin "42") (pinfunction "GND_42") (pintype "power_in"))
      (node (ref "U5") (pin "49") (pinfunction "GND_49") (pintype "power_in"))
      (node (ref "U5") (pin "5") (pinfunction "GND_5") (pintype "power_in"))
      (node (ref "U5") (pin "8") (pinfunction "AGND_8") (pintype "power_in"))
      (node (ref "U6") (pin "20") (pinfunction "GND_20") (pintype "power_in"))
      (node (ref "U6") (pin "23") (pinfunction "GND_23") (pintype "power_in"))
      (node (ref "U6") (pin "32") (pinfunction "GND_32") (pintype "power_in"))
      (node (ref "U6") (pin "38") (pinfunction "GND_38") (pintype "power_in"))
      (node (ref "U6") (pin "42") (pinfunction "GND_42") (pintype "power_in"))
      (node (ref "U6") (pin "49") (pinfunction "GND_49") (pintype "power_in"))
      (node (ref "U6") (pin "5") (pinfunction "GND_5") (pintype "power_in"))
      (node (ref "U6") (pin "8") (pinfunction "AGND_8") (pintype "power_in"))
      (node (ref "U7") (pin "20") (pinfunction "GND_20") (pintype "power_in"))
      (node (ref "U7") (pin "23") (pinfunction "GND_23") (pintype "power_in"))
      (node (ref "U7") (pin "32") (pinfunction "GND_32") (pintype "power_in"))
      (node (ref "U7") (pin "38") (pinfunction "GND_38") (pintype "power_in"))
      (node (ref "U7") (pin "42") (pinfunction "GND_42") (pintype "power_in"))
      (node (ref "U7") (pin "49") (pinfunction "GND_49") (pintype "power_in"))
      (node (ref "U7") (pin "5") (pinfunction "GND_5") (pintype "power_in"))
      (node (ref "U7") (pin "8") (pinfunction "AGND_8") (pintype "power_in"))
      (node (ref "U8") (pin "20") (pinfunction "GND_20") (pintype "power_in"))
      (node (ref "U8") (pin "23") (pinfunction "GND_23") (pintype "power_in"))
      (node (ref "U8") (pin "32") (pinfunction "GND_32") (pintype "power_in"))
      (node (ref "U8") (pin "38") (pinfunction "GND_38") (pintype "power_in"))
      (node (ref "U8") (pin "42") (pinfunction "GND_42") (pintype "power_in"))
      (node (ref "U8") (pin "49") (pinfunction "GND_49") (pintype "power_in"))
      (node (ref "U8") (pin "5") (pinfunction "GND_5") (pintype "power_in"))
      (node (ref "U8") (pin "8") (pinfunction "AGND_8") (pintype "power_in"))
      (node (ref "U9") (pin "20") (pinfunction "GND_20") (pintype "power_in"))
      (node (ref "U9") (pin "23") (pinfunction "GND_23") (pintype "power_in"))
      (node (ref "U9") (pin "32") (pinfunction "GND_32") (pintype "power_in"))
      (node (ref "U9") (pin "38") (pinfunction "GND_38") (pintype "power_in"))
      (node (ref "U9") (pin "42") (pinfunction "GND_42") (pintype "power_in"))
      (node (ref "U9") (pin "49") (pinfunction "GND_49") (pintype "power_in"))
      (node (ref "U9") (pin "5") (pinfunction "GND_5") (pintype "power_in"))
      (node (ref "U9") (pin "8") (pinfunction "AGND_8") (pintype "power_in"))
      (node (ref "Y1") (pin "2") (pinfunction "NC_2") (pintype "passive"))
    )
    (net (code "35") (name "Net-(P1-Pad12)") (class "Default")
      (node (ref "P1") (pin "12") (pinfunction "12_12") (pintype "passive"))
      (node (ref "R25") (pin "2") (pinfunction "2_2") (pintype "passive"))
    )
    (net (code "36") (name "Net-(U3-AVCC)") (class "Default")
      (node (ref "C46") (pin "1") (pinfunction "1_1") (pintype "passive"))
      (node (ref "M1") (pin "1") (pinfunction "1_1") (pintype "passive"))
      (node (ref "U3") (pin "7") (pinfunction "AVCC_7") (pintype "power_in"))
    )
    (net (code "37") (name "Net-(U3-RST_N)") (class "Default")
      (node (ref "C22") (pin "1") (pinfunction "1_1") (pintype "passive"))
      (node (ref "R12") (pin "1") (pinfunction "1_1") (pintype "passive"))
      (node (ref "U3") (pin "45") (pinfunction "RST_N_45") (pintype "input"))
    )
    (net (code "38") (name "Net-(U4-AVCC)") (class "Default")
      (node (ref "C47") (pin "1") (pinfunction "1_1") (pintype "passive"))
      (node (ref "M2") (pin "1") (pinfunction "1_1") (pintype "passive"))
      (node (ref "U4") (pin "7") (pinfunction "AVCC_7") (pintype "power_in"))
    )
    (net (code "39") (name "Net-(U4-RST_N)") (class "Default")
      (node (ref "C23") (pin "1") (pinfunction "1_1") (pintype "passive"))
      (node (ref "R13") (pin "1") (pinfunction "1_1") (pintype "passive"))
      (node (ref "U4") (pin "45") (pinfunction "RST_N_45") (pintype "input"))
    )
    (net (code "40") (name "Net-(U5-AVCC)") (class "Default")
      (node (ref "C48") (pin "1") (pinfunction "1_1") (pintype "passive"))
      (node (ref "M3") (pin "1") (pinfunction "1_1") (pintype "passive"))
      (node (ref "U5") (pin "7") (pinfunction "AVCC_7") (pintype "power_in"))
    )
    (net (code "41") (name "Net-(U5-RST_N)") (class "Default")
      (node (ref "C24") (pin "1") (pinfunction "1_1") (pintype "passive"))
      (node (ref "R14") (pin "1") (pinfunction "1_1") (pintype "passive"))
      (node (ref "U5") (pin "45") (pinfunction "RST_N_45") (pintype "input"))
    )
    (net (code "42") (name "Net-(U6-AVCC)") (class "Default")
      (node (ref "C49") (pin "1") (pinfunction "1_1") (pintype "passive"))
      (node (ref "M4") (pin "1") (pinfunction "1_1") (pintype "passive"))
      (node (ref "U6") (pin "7") (pinfunction "AVCC_7") (pintype "power_in"))
    )
    (net (code "43") (name "Net-(U6-RST_N)") (class "Default")
      (node (ref "C25") (pin "1") (pinfunction "1_1") (pintype "passive"))
      (node (ref "R15") (pin "1") (pinfunction "1_1") (pintype "passive"))
      (node (ref "U6") (pin "45") (pinfunction "RST_N_45") (pintype "input"))
    )
    (net (code "44") (name "Net-(U7-AVCC)") (class "Default")
      (node (ref "C94") (pin "1") (pinfunction "1_1") (pintype "passive"))
      (node (ref "M5") (pin "1") (pinfunction "1_1") (pintype "passive"))
      (node (ref "U7") (pin "7") (pinfunction "AVCC_7") (pintype "power_in"))
    )
    (net (code "45") (name "Net-(U7-RST_N)") (class "Default")
      (node (ref "C70") (pin "1") (pinfunction "1_1") (pintype "passive"))
      (node (ref "R16") (pin "1") (pinfunction "1_1") (pintype "passive"))
      (node (ref "U7") (pin "45") (pinfunction "RST_N_45") (pintype "input"))
    )
    (net (code "46") (name "Net-(U8-AVCC)") (class "Default")
      (node (ref "C95") (pin "1") (pinfunction "1_1") (pintype "passive"))
      (node (ref "M6") (pin "1") (pinfunction "1_1") (pintype "passive"))
      (node (ref "U8") (pin "7") (pinfunction "AVCC_7") (pintype "power_in"))
    )
    (net (code "47") (name "Net-(U8-RST_N)") (class "Default")
      (node (ref "C71") (pin "1") (pinfunction "1_1") (pintype "passive"))
      (node (ref "R17") (pin "1") (pinfunction "1_1") (pintype "passive"))
      (node (ref "U8") (pin "45") (pinfunction "RST_N_45") (pintype "input"))
    )
    (net (code "48") (name "Net-(U9-AVCC)") (class "Default")
      (node (ref "C96") (pin "1") (pinfunction "1_1") (pintype "passive"))
      (node (ref "M7") (pin "1") (pinfunction "1_1") (pintype "passive"))
      (node (ref "U9") (pin "7") (pinfunction "AVCC_7") (pintype "power_in"))
    )
    (net (code "49") (name "Net-(U9-RST_N)") (class "Default")
      (node (ref "C72") (pin "1") (pinfunction "1_1") (pintype "passive"))
      (node (ref "R18") (pin "1") (pinfunction "1_1") (pintype "passive"))
      (node (ref "U9") (pin "45") (pinfunction "RST_N_45") (pintype "input"))
    )
    (net (code "50") (name "Net-(U10-AVCC)") (class "Default")
      (node (ref "C97") (pin "1") (pinfunction "1_1") (pintype "passive"))
      (node (ref "M8") (pin "1") (pinfunction "1_1") (pintype "passive"))
      (node (ref "U10") (pin "7") (pinfunction "AVCC_7") (pintype "power_in"))
    )
    (net (code "51") (name "Net-(U10-RST_N)") (class "Default")
      (node (ref "C73") (pin "1") (pinfunction "1_1") (pintype "passive"))
      (node (ref "R19") (pin "1") (pinfunction "1_1") (pintype "passive"))
      (node (ref "U10") (pin "45") (pinfunction "RST_N_45") (pintype "input"))
    )
    (net (code "52") (name "Net-(U11-AVCC)") (class "Default")
      (node (ref "C133") (pin "1") (pinfunction "1_1") (pintype "passive"))
      (node (ref "M10") (pin "1") (pinfunction "1_1") (pintype "passive"))
      (node (ref "U11") (pin "7") (pinfunction "AVCC_7") (pintype "power_in"))
    )
    (net (code "53") (name "Net-(U11-RST_N)") (class "Default")
      (node (ref "C118") (pin "1") (pinfunction "1_1") (pintype "passive"))
      (node (ref "R20") (pin "1") (pinfunction "1_1") (pintype "passive"))
      (node (ref "U11") (pin "45") (pinfunction "RST_N_45") (pintype "input"))
    )
    (net (code "54") (name "Net-(U12-AVCC)") (class "Default")
      (node (ref "C134") (pin "1") (pinfunction "1_1") (pintype "passive"))
      (node (ref "M11") (pin "1") (pinfunction "1_1") (pintype "passive"))
      (node (ref "U12") (pin "7") (pinfunction "AVCC_7") (pintype "power_in"))
    )
    (net (code "55") (name "Net-(U12-RST_N)") (class "Default")
      (node (ref "C119") (pin "1") (pinfunction "1_1") (pintype "passive"))
      (node (ref "R21") (pin "1") (pinfunction "1_1") (pintype "passive"))
      (node (ref "U12") (pin "45") (pinfunction "RST_N_45") (pintype "input"))
    )
    (net (code "56") (name "Net-(U13-1Y)") (class "Default")
      (node (ref "P1") (pin "10") (pinfunction "10_10") (pintype "passive"))
      (node (ref "U13") (pin "6") (pinfunction "1Y_6") (pintype "output"))
    )
    (net (code "57") (name "Net-(U13-2Y)") (class "Default")
      (node (ref "P1") (pin "8") (pinfunction "8_8") (pintype "passive"))
      (node (ref "U13") (pin "4") (pinfunction "2Y_4") (pintype "output"))
    )
    (net (code "58") (name "Net-(U14-1A)") (class "Default")
      (node (ref "P1") (pin "4") (pinfunction "4_4") (pintype "passive"))
      (node (ref "U14") (pin "1") (pinfunction "1A_1") (pintype "input"))
    )
    (net (code "59") (name "Net-(U14-2A)") (class "Default")
      (node (ref "P1") (pin "6") (pinfunction "6_6") (pintype "passive"))
      (node (ref "U14") (pin "3") (pinfunction "2A_3") (pintype "input"))
    )
    (net (code "60") (name "Net-(U15-1Y)") (class "Default")
      (node (ref "R26") (pin "2") (pinfunction "2_2") (pintype "passive"))
      (node (ref "U15") (pin "6") (pinfunction "1Y_6") (pintype "output"))
    )
    (net (code "61") (name "Net-(U15-2Y)") (class "Default")
      (node (ref "R27") (pin "2") (pinfunction "2_2") (pintype "passive"))
      (node (ref "U15") (pin "4") (pinfunction "2Y_4") (pintype "output"))
    )
    (net (code "62") (name "Net-(Y1-OSC1)") (class "Default")
      (node (ref "C127") (pin "2") (pinfunction "2_2") (pintype "passive"))
      (node (ref "M9") (pin "1") (pinfunction "1_1") (pintype "passive"))
      (node (ref "Y1") (pin "1") (pinfunction "OSC1_1") (pintype "passive"))
      (node (ref "Y1") (pin "4") (pinfunction "NC_4") (pintype "passive"))
    )
    (net (code "63") (name "Net-(Y1-OSC2)") (class "Default")
      (node (ref "R22") (pin "2") (pinfunction "2_2") (pintype "passive"))
      (node (ref "Y1") (pin "3") (pinfunction "OSC2_3") (pintype "passive"))
    )
    (net (code "64") (name "VCC1V2") (class "Default")
      (node (ref "C100") (pin "2") (pinfunction "2_2") (pintype "passive"))
      (node (ref "C101") (pin "2") (pinfunction "2_2") (pintype "passive"))
      (node (ref "C102") (pin "1") (pinfunction "1_1") (pintype "passive"))
      (node (ref "C103") (pin "1") (pinfunction "1_1") (pintype "passive"))
      (node (ref "C104") (pin "1") (pinfunction "1_1") (pintype "passive"))
      (node (ref "C105") (pin "1") (pinfunction "1_1") (pintype "passive"))
      (node (ref "C106") (pin "2") (pinfunction "2_2") (pintype "passive"))
      (node (ref "C107") (pin "2") (pinfunction "2_2") (pintype "passive"))
      (node (ref "C109") (pin "2") (pinfunction "2_2") (pintype "passive"))
      (node (ref "C110") (pin "2") (pinfunction "2_2") (pintype "passive"))
      (node (ref "C112") (pin "2") (pinfunction "2_2") (pintype "passive"))
      (node (ref "C113") (pin "2") (pinfunction "2_2") (pintype "passive"))
      (node (ref "C115") (pin "2") (pinfunction "2_2") (pintype "passive"))
      (node (ref "C116") (pin "2") (pinfunction "2_2") (pintype "passive"))
      (node (ref "C120") (pin "1") (pinfunction "1_1") (pintype "passive"))
      (node (ref "C121") (pin "2") (pinfunction "2_2") (pintype "passive"))
      (node (ref "C122") (pin "1") (pinfunction "1_1") (pintype "passive"))
      (node (ref "C123") (pin "2") (pinfunction "2_2") (pintype "passive"))
      (node (ref "C128") (pin "1") (pinfunction "1_1") (pintype "passive"))
      (node (ref "C129") (pin "2") (pinfunction "2_2") (pintype "passive"))
      (node (ref "C130") (pin "1") (pinfunction "1_1") (pintype "passive"))
      (node (ref "C131") (pin "2") (pinfunction "2_2") (pintype "passive"))
      (node (ref "C135") (pin "2") (pinfunction "2_2") (pintype "passive"))
      (node (ref "C136") (pin "2") (pinfunction "2_2") (pintype "passive"))
      (node (ref "C138") (pin "1") (pinfunction "1_1") (pintype "passive"))
      (node (ref "C139") (pin "1") (pinfunction "1_1") (pintype "passive"))
      (node (ref "C140") (pin "2") (pinfunction "2_2") (pintype "passive"))
      (node (ref "C141") (pin "2") (pinfunction "2_2") (pintype "passive"))
      (node (ref "C143") (pin "2") (pinfunction "2_2") (pintype "passive"))
      (node (ref "C144") (pin "2") (pinfunction "2_2") (pintype "passive"))
      (node (ref "C26") (pin "1") (pinfunction "1_1") (pintype "passive"))
      (node (ref "C27") (pin "2") (pinfunction "2_2") (pintype "passive"))
      (node (ref "C28") (pin "1") (pinfunction "1_1") (pintype "passive"))
      (node (ref "C29") (pin "2") (pinfunction "2_2") (pintype "passive"))
      (node (ref "C30") (pin "1") (pinfunction "1_1") (pintype "passive"))
      (node (ref "C31") (pin "2") (pinfunction "2_2") (pintype "passive"))
      (node (ref "C32") (pin "1") (pinfunction "1_1") (pintype "passive"))
      (node (ref "C33") (pin "2") (pinfunction "2_2") (pintype "passive"))
      (node (ref "C38") (pin "1") (pinfunction "1_1") (pintype "passive"))
      (node (ref "C39") (pin "2") (pinfunction "2_2") (pintype "passive"))
      (node (ref "C40") (pin "1") (pinfunction "1_1") (pintype "passive"))
      (node (ref "C41") (pin "2") (pinfunction "2_2") (pintype "passive"))
      (node (ref "C42") (pin "1") (pinfunction "1_1") (pintype "passive"))
      (node (ref "C43") (pin "2") (pinfunction "2_2") (pintype "passive"))
      (node (ref "C44") (pin "1") (pinfunction "1_1") (pintype "passive"))
      (node (ref "C45") (pin "2") (pinfunction "2_2") (pintype "passive"))
      (node (ref "C50") (pin "2") (pinfunction "2_2") (pintype "passive"))
      (node (ref "C51") (pin "2") (pinfunction "2_2") (pintype "passive"))
      (node (ref "C52") (pin "2") (pinfunction "2_2") (pintype "passive"))
      (node (ref "C53") (pin "2") (pinfunction "2_2") (pintype "passive"))
      (node (ref "C54") (pin "1") (pinfunction "1_1") (pintype "passive"))
      (node (ref "C55") (pin "1") (pinfunction "1_1") (pintype "passive"))
      (node (ref "C56") (pin "1") (pinfunction "1_1") (pintype "passive"))
      (node (ref "C57") (pin "1") (pinfunction "1_1") (pintype "passive"))
      (node (ref "C58") (pin "2") (pinfunction "2_2") (pintype "passive"))
      (node (ref "C59") (pin "2") (pinfunction "2_2") (pintype "passive"))
      (node (ref "C61") (pin "2") (pinfunction "2_2") (pintype "passive"))
      (node (ref "C62") (pin "2") (pinfunction "2_2") (pintype "passive"))
      (node (ref "C64") (pin "2") (pinfunction "2_2") (pintype "passive"))
      (node (ref "C65") (pin "2") (pinfunction "2_2") (pintype "passive"))
      (node (ref "C67") (pin "2") (pinfunction "2_2") (pintype "passive"))
      (node (ref "C68") (pin "2") (pinfunction "2_2") (pintype "passive"))
      (node (ref "C74") (pin "1") (pinfunction "1_1") (pintype "passive"))
      (node (ref "C75") (pin "2") (pinfunction "2_2") (pintype "passive"))
      (node (ref "C76") (pin "1") (pinfunction "1_1") (pintype "passive"))
      (node (ref "C77") (pin "2") (pinfunction "2_2") (pintype "passive"))
      (node (ref "C78") (pin "1") (pinfunction "1_1") (pintype "passive"))
      (node (ref "C79") (pin "2") (pinfunction "2_2") (pintype "passive"))
      (node (ref "C80") (pin "1") (pinfunction "1_1") (pintype "passive"))
      (node (ref "C81") (pin "2") (pinfunction "2_2") (pintype "passive"))
      (node (ref "C86") (pin "1") (pinfunction "1_1") (pintype "passive"))
      (node (ref "C87") (pin "2") (pinfunction "2_2") (pintype "passive"))
      (node (ref "C88") (pin "1") (pinfunction "1_1") (pintype "passive"))
      (node (ref "C89") (pin "2") (pinfunction "2_2") (pintype "passive"))
      (node (ref "C90") (pin "1") (pinfunction "1_1") (pintype "passive"))
      (node (ref "C91") (pin "2") (pinfunction "2_2") (pintype "passive"))
      (node (ref "C92") (pin "1") (pinfunction "1_1") (pintype "passive"))
      (node (ref "C93") (pin "2") (pinfunction "2_2") (pintype "passive"))
      (node (ref "C98") (pin "2") (pinfunction "2_2") (pintype "passive"))
      (node (ref "C99") (pin "2") (pinfunction "2_2") (pintype "passive"))
      (node (ref "U10") (pin "11") (pinfunction "VCC_11") (pintype "power_in"))
      (node (ref "U10") (pin "12") (pinfunction "VCC_12") (pintype "power_in"))
      (node (ref "U10") (pin "13") (pinfunction "VCC_13") (pintype "power_in"))
      (node (ref "U10") (pin "14") (pinfunction "VCC_14") (pintype "power_in"))
      (node (ref "U10") (pin "15") (pinfunction "VCC_15") (pintype "power_in"))
      (node (ref "U10") (pin "16") (pinfunction "VCC_16") (pintype "power_in"))
      (node (ref "U10") (pin "19") (pinfunction "VCC_19") (pintype "power_in"))
      (node (ref "U10") (pin "21") (pinfunction "VCC_21") (pintype "power_in"))
      (node (ref "U10") (pin "22") (pinfunction "VCC_22") (pintype "power_in"))
      (node (ref "U10") (pin "25") (pinfunction "VCC_25") (pintype "power_in"))
      (node (ref "U10") (pin "26") (pinfunction "VCC_26") (pintype "power_in"))
      (node (ref "U10") (pin "27") (pinfunction "VCC_27") (pintype "power_in"))
      (node (ref "U10") (pin "28") (pinfunction "VCC_28") (pintype "power_in"))
      (node (ref "U10") (pin "3") (pinfunction "VCC_3") (pintype "power_in"))
      (node (ref "U10") (pin "31") (pinfunction "VCC_31") (pintype "power_in"))
      (node (ref "U10") (pin "33") (pinfunction "VCC_33") (pintype "power_in"))
      (node (ref "U10") (pin "34") (pinfunction "VCC_34") (pintype "power_in"))
      (node (ref "U10") (pin "39") (pinfunction "VCC_39") (pintype "power_in"))
      (node (ref "U10") (pin "4") (pinfunction "VCC_4") (pintype "power_in"))
      (node (ref "U10") (pin "40") (pinfunction "VCC_40") (pintype "power_in"))
      (node (ref "U10") (pin "41") (pinfunction "VCC_41") (pintype "power_in"))
      (node (ref "U10") (pin "43") (pinfunction "VCC_43") (pintype "power_in"))
      (node (ref "U10") (pin "46") (pinfunction "VCC_46") (pintype "power_in"))
      (node (ref "U10") (pin "47") (pinfunction "VCC_47") (pintype "power_in"))
      (node (ref "U10") (pin "48") (pinfunction "VCC_48") (pintype "power_in"))
      (node (ref "U10") (pin "6") (pinfunction "VCC_6") (pintype "power_in"))
      (node (ref "U11") (pin "11") (pinfunction "VCC_11") (pintype "power_in"))
      (node (ref "U11") (pin "12") (pinfunction "VCC_12") (pintype "power_in"))
      (node (ref "U11") (pin "13") (pinfunction "VCC_13") (pintype "power_in"))
      (node (ref "U11") (pin "14") (pinfunction "VCC_14") (pintype "power_in"))
      (node (ref "U11") (pin "15") (pinfunction "VCC_15") (pintype "power_in"))
      (node (ref "U11") (pin "16") (pinfunction "VCC_16") (pintype "power_in"))
      (node (ref "U11") (pin "19") (pinfunction "VCC_19") (pintype "power_in"))
      (node (ref "U11") (pin "21") (pinfunction "VCC_21") (pintype "power_in"))
      (node (ref "U11") (pin "22") (pinfunction "VCC_22") (pintype "power_in"))
      (node (ref "U11") (pin "25") (pinfunction "VCC_25") (pintype "power_in"))
      (node (ref "U11") (pin "26") (pinfunction "VCC_26") (pintype "power_in"))
      (node (ref "U11") (pin "27") (pinfunction "VCC_27") (pintype "power_in"))
      (node (ref "U11") (pin "28") (pinfunction "VCC_28") (pintype "power_in"))
      (node (ref "U11") (pin "3") (pinfunction "VCC_3") (pintype "power_in"))
      (node (ref "U11") (pin "31") (pinfunction "VCC_31") (pintype "power_in"))
      (node (ref "U11") (pin "33") (pinfunction "VCC_33") (pintype "power_in"))
      (node (ref "U11") (pin "34") (pinfunction "VCC_34") (pintype "power_in"))
      (node (ref "U11") (pin "39") (pinfunction "VCC_39") (pintype "power_in"))
      (node (ref "U11") (pin "4") (pinfunction "VCC_4") (pintype "power_in"))
      (node (ref "U11") (pin "40") (pinfunction "VCC_40") (pintype "power_in"))
      (node (ref "U11") (pin "41") (pinfunction "VCC_41") (pintype "power_in"))
      (node (ref "U11") (pin "43") (pinfunction "VCC_43") (pintype "power_in"))
      (node (ref "U11") (pin "46") (pinfunction "VCC_46") (pintype "power_in"))
      (node (ref "U11") (pin "47") (pinfunction "VCC_47") (pintype "power_in"))
      (node (ref "U11") (pin "48") (pinfunction "VCC_48") (pintype "power_in"))
      (node (ref "U11") (pin "6") (pinfunction "VCC_6") (pintype "power_in"))
      (node (ref "U12") (pin "11") (pinfunction "VCC_11") (pintype "power_in"))
      (node (ref "U12") (pin "12") (pinfunction "VCC_12") (pintype "power_in"))
      (node (ref "U12") (pin "13") (pinfunction "VCC_13") (pintype "power_in"))
      (node (ref "U12") (pin "14") (pinfunction "VCC_14") (pintype "power_in"))
      (node (ref "U12") (pin "15") (pinfunction "VCC_15") (pintype "power_in"))
      (node (ref "U12") (pin "16") (pinfunction "VCC_16") (pintype "power_in"))
      (node (ref "U12") (pin "19") (pinfunction "VCC_19") (pintype "power_in"))
      (node (ref "U12") (pin "21") (pinfunction "VCC_21") (pintype "power_in"))
      (node (ref "U12") (pin "22") (pinfunction "VCC_22") (pintype "power_in"))
      (node (ref "U12") (pin "25") (pinfunction "VCC_25") (pintype "power_in"))
      (node (ref "U12") (pin "26") (pinfunction "VCC_26") (pintype "power_in"))
      (node (ref "U12") (pin "27") (pinfunction "VCC_27") (pintype "power_in"))
      (node (ref "U12") (pin "28") (pinfunction "VCC_28") (pintype "power_in"))
      (node (ref "U12") (pin "3") (pinfunction "VCC_3") (pintype "power_in"))
      (node (ref "U12") (pin "31") (pinfunction "VCC_31") (pintype "power_in"))
      (node (ref "U12") (pin "33") (pinfunction "VCC_33") (pintype "power_in"))
      (node (ref "U12") (pin "34") (pinfunction "VCC_34") (pintype "power_in"))
      (node (ref "U12") (pin "39") (pinfunction "VCC_39") (pintype "power_in"))
      (node (ref "U12") (pin "4") (pinfunction "VCC_4") (pintype "power_in"))
      (node (ref "U12") (pin "40") (pinfunction "VCC_40") (pintype "power_in"))
      (node (ref "U12") (pin "41") (pinfunction "VCC_41") (pintype "power_in"))
      (node (ref "U12") (pin "43") (pinfunction "VCC_43") (pintype "power_in"))
      (node (ref "U12") (pin "46") (pinfunction "VCC_46") (pintype "power_in"))
      (node (ref "U12") (pin "47") (pinfunction "VCC_47") (pintype "power_in"))
      (node (ref "U12") (pin "48") (pinfunction "VCC_48") (pintype "power_in"))
      (node (ref "U12") (pin "6") (pinfunction "VCC_6") (pintype "power_in"))
      (node (ref "U3") (pin "11") (pinfunction "VCC_11") (pintype "power_in"))
      (node (ref "U3") (pin "12") (pinfunction "VCC_12") (pintype "power_in"))
      (node (ref "U3") (pin "13") (pinfunction "VCC_13") (pintype "power_in"))
      (node (ref "U3") (pin "14") (pinfunction "VCC_14") (pintype "power_in"))
      (node (ref "U3") (pin "15") (pinfunction "VCC_15") (pintype "power_in"))
      (node (ref "U3") (pin "16") (pinfunction "VCC_16") (pintype "power_in"))
      (node (ref "U3") (pin "19") (pinfunction "VCC_19") (pintype "power_in"))
      (node (ref "U3") (pin "21") (pinfunction "VCC_21") (pintype "power_in"))
      (node (ref "U3") (pin "22") (pinfunction "VCC_22") (pintype "power_in"))
      (node (ref "U3") (pin "25") (pinfunction "VCC_25") (pintype "power_in"))
      (node (ref "U3") (pin "26") (pinfunction "VCC_26") (pintype "power_in"))
      (node (ref "U3") (pin "27") (pinfunction "VCC_27") (pintype "power_in"))
      (node (ref "U3") (pin "28") (pinfunction "VCC_28") (pintype "power_in"))
      (node (ref "U3") (pin "3") (pinfunction "VCC_3") (pintype "power_in"))
      (node (ref "U3") (pin "31") (pinfunction "VCC_31") (pintype "power_in"))
      (node (ref "U3") (pin "33") (pinfunction "VCC_33") (pintype "power_in"))
      (node (ref "U3") (pin "34") (pinfunction "VCC_34") (pintype "power_in"))
      (node (ref "U3") (pin "39") (pinfunction "VCC_39") (pintype "power_in"))
      (node (ref "U3") (pin "4") (pinfunction "VCC_4") (pintype "power_in"))
      (node (ref "U3") (pin "40") (pinfunction "VCC_40") (pintype "power_in"))
      (node (ref "U3") (pin "41") (pinfunction "VCC_41") (pintype "power_in"))
      (node (ref "U3") (pin "43") (pinfunction "VCC_43") (pintype "power_in"))
      (node (ref "U3") (pin "46") (pinfunction "VCC_46") (pintype "power_in"))
      (node (ref "U3") (pin "47") (pinfunction "VCC_47") (pintype "power_in"))
      (node (ref "U3") (pin "48") (pinfunction "VCC_48") (pintype "power_in"))
      (node (ref "U3") (pin "6") (pinfunction "VCC_6") (pintype "power_in"))
      (node (ref "U4") (pin "11") (pinfunction "VCC_11") (pintype "power_in"))
      (node (ref "U4") (pin "12") (pinfunction "VCC_12") (pintype "power_in"))
      (node (ref "U4") (pin "13") (pinfunction "VCC_13") (pintype "power_in"))
      (node (ref "U4") (pin "14") (pinfunction "VCC_14") (pintype "power_in"))
      (node (ref "U4") (pin "15") (pinfunction "VCC_15") (pintype "power_in"))
      (node (ref "U4") (pin "16") (pinfunction "VCC_16") (pintype "power_in"))
      (node (ref "U4") (pin "19") (pinfunction "VCC_19") (pintype "power_in"))
      (node (ref "U4") (pin "21") (pinfunction "VCC_21") (pintype "power_in"))
      (node (ref "U4") (pin "22") (pinfunction "VCC_22") (pintype "power_in"))
      (node (ref "U4") (pin "25") (pinfunction "VCC_25") (pintype "power_in"))
      (node (ref "U4") (pin "26") (pinfunction "VCC_26") (pintype "power_in"))
      (node (ref "U4") (pin "27") (pinfunction "VCC_27") (pintype "power_in"))
      (node (ref "U4") (pin "28") (pinfunction "VCC_28") (pintype "power_in"))
      (node (ref "U4") (pin "3") (pinfunction "VCC_3") (pintype "power_in"))
      (node (ref "U4") (pin "31") (pinfunction "VCC_31") (pintype "power_in"))
      (node (ref "U4") (pin "33") (pinfunction "VCC_33") (pintype "power_in"))
      (node (ref "U4") (pin "34") (pinfunction "VCC_34") (pintype "power_in"))
      (node (ref "U4") (pin "39") (pinfunction "VCC_39") (pintype "power_in"))
      (node (ref "U4") (pin "4") (pinfunction "VCC_4") (pintype "power_in"))
      (node (ref "U4") (pin "40") (pinfunction "VCC_40") (pintype "power_in"))
      (node (ref "U4") (pin "41") (pinfunction "VCC_41") (pintype "power_in"))
      (node (ref "U4") (pin "43") (pinfunction "VCC_43") (pintype "power_in"))
      (node (ref "U4") (pin "46") (pinfunction "VCC_46") (pintype "power_in"))
      (node (ref "U4") (pin "47") (pinfunction "VCC_47") (pintype "power_in"))
      (node (ref "U4") (pin "48") (pinfunction "VCC_48") (pintype "power_in"))
      (node (ref "U4") (pin "6") (pinfunction "VCC_6") (pintype "power_in"))
      (node (ref "U5") (pin "11") (pinfunction "VCC_11") (pintype "power_in"))
      (node (ref "U5") (pin "12") (pinfunction "VCC_12") (pintype "power_in"))
      (node (ref "U5") (pin "13") (pinfunction "VCC_13") (pintype "power_in"))
      (node (ref "U5") (pin "14") (pinfunction "VCC_14") (pintype "power_in"))
      (node (ref "U5") (pin "15") (pinfunction "VCC_15") (pintype "power_in"))
      (node (ref "U5") (pin "16") (pinfunction "VCC_16") (pintype "power_in"))
      (node (ref "U5") (pin "19") (pinfunction "VCC_19") (pintype "power_in"))
      (node (ref "U5") (pin "21") (pinfunction "VCC_21") (pintype "power_in"))
      (node (ref "U5") (pin "22") (pinfunction "VCC_22") (pintype "power_in"))
      (node (ref "U5") (pin "25") (pinfunction "VCC_25") (pintype "power_in"))
      (node (ref "U5") (pin "26") (pinfunction "VCC_26") (pintype "power_in"))
      (node (ref "U5") (pin "27") (pinfunction "VCC_27") (pintype "power_in"))
      (node (ref "U5") (pin "28") (pinfunction "VCC_28") (pintype "power_in"))
      (node (ref "U5") (pin "3") (pinfunction "VCC_3") (pintype "power_in"))
      (node (ref "U5") (pin "31") (pinfunction "VCC_31") (pintype "power_in"))
      (node (ref "U5") (pin "33") (pinfunction "VCC_33") (pintype "power_in"))
      (node (ref "U5") (pin "34") (pinfunction "VCC_34") (pintype "power_in"))
      (node (ref "U5") (pin "39") (pinfunction "VCC_39") (pintype "power_in"))
      (node (ref "U5") (pin "4") (pinfunction "VCC_4") (pintype "power_in"))
      (node (ref "U5") (pin "40") (pinfunction "VCC_40") (pintype "power_in"))
      (node (ref "U5") (pin "41") (pinfunction "VCC_41") (pintype "power_in"))
      (node (ref "U5") (pin "43") (pinfunction "VCC_43") (pintype "power_in"))
      (node (ref "U5") (pin "46") (pinfunction "VCC_46") (pintype "power_in"))
      (node (ref "U5") (pin "47") (pinfunction "VCC_47") (pintype "power_in"))
      (node (ref "U5") (pin "48") (pinfunction "VCC_48") (pintype "power_in"))
      (node (ref "U5") (pin "6") (pinfunction "VCC_6") (pintype "power_in"))
      (node (ref "U6") (pin "11") (pinfunction "VCC_11") (pintype "power_in"))
      (node (ref "U6") (pin "12") (pinfunction "VCC_12") (pintype "power_in"))
      (node (ref "U6") (pin "13") (pinfunction "VCC_13") (pintype "power_in"))
      (node (ref "U6") (pin "14") (pinfunction "VCC_14") (pintype "power_in"))
      (node (ref "U6") (pin "15") (pinfunction "VCC_15") (pintype "power_in"))
      (node (ref "U6") (pin "16") (pinfunction "VCC_16") (pintype "power_in"))
      (node (ref "U6") (pin "19") (pinfunction "VCC_19") (pintype "power_in"))
      (node (ref "U6") (pin "21") (pinfunction "VCC_21") (pintype "power_in"))
      (node (ref "U6") (pin "22") (pinfunction "VCC_22") (pintype "power_in"))
      (node (ref "U6") (pin "25") (pinfunction "VCC_25") (pintype "power_in"))
      (node (ref "U6") (pin "26") (pinfunction "VCC_26") (pintype "power_in"))
      (node (ref "U6") (pin "27") (pinfunction "VCC_27") (pintype "power_in"))
      (node (ref "U6") (pin "28") (pinfunction "VCC_28") (pintype "power_in"))
      (node (ref "U6") (pin "3") (pinfunction "VCC_3") (pintype "power_in"))
      (node (ref "U6") (pin "31") (pinfunction "VCC_31") (pintype "power_in"))
      (node (ref "U6") (pin "33") (pinfunction "VCC_33") (pintype "power_in"))
      (node (ref "U6") (pin "34") (pinfunction "VCC_34") (pintype "power_in"))
      (node (ref "U6") (pin "39") (pinfunction "VCC_39") (pintype "power_in"))
      (node (ref "U6") (pin "4") (pinfunction "VCC_4") (pintype "power_in"))
      (node (ref "U6") (pin "40") (pinfunction "VCC_40") (pintype "power_in"))
      (node (ref "U6") (pin "41") (pinfunction "VCC_41") (pintype "power_in"))
      (node (ref "U6") (pin "43") (pinfunction "VCC_43") (pintype "power_in"))
      (node (ref "U6") (pin "46") (pinfunction "VCC_46") (pintype "power_in"))
      (node (ref "U6") (pin "47") (pinfunction "VCC_47") (pintype "power_in"))
      (node (ref "U6") (pin "48") (pinfunction "VCC_48") (pintype "power_in"))
      (node (ref "U6") (pin "6") (pinfunction "VCC_6") (pintype "power_in"))
      (node (ref "U7") (pin "11") (pinfunction "VCC_11") (pintype "power_in"))
      (node (ref "U7") (pin "12") (pinfunction "VCC_12") (pintype "power_in"))
      (node (ref "U7") (pin "13") (pinfunction "VCC_13") (pintype "power_in"))
      (node (ref "U7") (pin "14") (pinfunction "VCC_14") (pintype "power_in"))
      (node (ref "U7") (pin "15") (pinfunction "VCC_15") (pintype "power_in"))
      (node (ref "U7") (pin "16") (pinfunction "VCC_16") (pintype "power_in"))
      (node (ref "U7") (pin "19") (pinfunction "VCC_19") (pintype "power_in"))
      (node (ref "U7") (pin "21") (pinfunction "VCC_21") (pintype "power_in"))
      (node (ref "U7") (pin "22") (pinfunction "VCC_22") (pintype "power_in"))
      (node (ref "U7") (pin "25") (pinfunction "VCC_25") (pintype "power_in"))
      (node (ref "U7") (pin "26") (pinfunction "VCC_26") (pintype "power_in"))
      (node (ref "U7") (pin "27") (pinfunction "VCC_27") (pintype "power_in"))
      (node (ref "U7") (pin "28") (pinfunction "VCC_28") (pintype "power_in"))
      (node (ref "U7") (pin "3") (pinfunction "VCC_3") (pintype "power_in"))
      (node (ref "U7") (pin "31") (pinfunction "VCC_31") (pintype "power_in"))
      (node (ref "U7") (pin "33") (pinfunction "VCC_33") (pintype "power_in"))
      (node (ref "U7") (pin "34") (pinfunction "VCC_34") (pintype "power_in"))
      (node (ref "U7") (pin "39") (pinfunction "VCC_39") (pintype "power_in"))
      (node (ref "U7") (pin "4") (pinfunction "VCC_4") (pintype "power_in"))
      (node (ref "U7") (pin "40") (pinfunction "VCC_40") (pintype "power_in"))
      (node (ref "U7") (pin "41") (pinfunction "VCC_41") (pintype "power_in"))
      (node (ref "U7") (pin "43") (pinfunction "VCC_43") (pintype "power_in"))
      (node (ref "U7") (pin "46") (pinfunction "VCC_46") (pintype "power_in"))
      (node (ref "U7") (pin "47") (pinfunction "VCC_47") (pintype "power_in"))
      (node (ref "U7") (pin "48") (pinfunction "VCC_48") (pintype "power_in"))
      (node (ref "U7") (pin "6") (pinfunction "VCC_6") (pintype "power_in"))
      (node (ref "U8") (pin "11") (pinfunction "VCC_11") (pintype "power_in"))
      (node (ref "U8") (pin "12") (pinfunction "VCC_12") (pintype "power_in"))
      (node (ref "U8") (pin "13") (pinfunction "VCC_13") (pintype "power_in"))
      (node (ref "U8") (pin "14") (pinfunction "VCC_14") (pintype "power_in"))
      (node (ref "U8") (pin "15") (pinfunction "VCC_15") (pintype "power_in"))
      (node (ref "U8") (pin "16") (pinfunction "VCC_16") (pintype "power_in"))
      (node (ref "U8") (pin "19") (pinfunction "VCC_19") (pintype "power_in"))
      (node (ref "U8") (pin "21") (pinfunction "VCC_21") (pintype "power_in"))
      (node (ref "U8") (pin "22") (pinfunction "VCC_22") (pintype "power_in"))
      (node (ref "U8") (pin "25") (pinfunction "VCC_25") (pintype "power_in"))
      (node (ref "U8") (pin "26") (pinfunction "VCC_26") (pintype "power_in"))
      (node (ref "U8") (pin "27") (pinfunction "VCC_27") (pintype "power_in"))
      (node (ref "U8") (pin "28") (pinfunction "VCC_28") (pintype "power_in"))
      (node (ref "U8") (pin "3") (pinfunction "VCC_3") (pintype "power_in"))
      (node (ref "U8") (pin "31") (pinfunction "VCC_31") (pintype "power_in"))
      (node (ref "U8") (pin "33") (pinfunction "VCC_33") (pintype "power_in"))
      (node (ref "U8") (pin "34") (pinfunction "VCC_34") (pintype "power_in"))
      (node (ref "U8") (pin "39") (pinfunction "VCC_39") (pintype "power_in"))
      (node (ref "U8") (pin "4") (pinfunction "VCC_4") (pintype "power_in"))
      (node (ref "U8") (pin "40") (pinfunction "VCC_40") (pintype "power_in"))
      (node (ref "U8") (pin "41") (pinfunction "VCC_41") (pintype "power_in"))
      (node (ref "U8") (pin "43") (pinfunction "VCC_43") (pintype "power_in"))
      (node (ref "U8") (pin "46") (pinfunction "VCC_46") (pintype "power_in"))
      (node (ref "U8") (pin "47") (pinfunction "VCC_47") (pintype "power_in"))
      (node (ref "U8") (pin "48") (pinfunction "VCC_48") (pintype "power_in"))
      (node (ref "U8") (pin "6") (pinfunction "VCC_6") (pintype "power_in"))
      (node (ref "U9") (pin "11") (pinfunction "VCC_11") (pintype "power_in"))
      (node (ref "U9") (pin "12") (pinfunction "VCC_12") (pintype "power_in"))
      (node (ref "U9") (pin "13") (pinfunction "VCC_13") (pintype "power_in"))
      (node (ref "U9") (pin "14") (pinfunction "VCC_14") (pintype "power_in"))
      (node (ref "U9") (pin "15") (pinfunction "VCC_15") (pintype "power_in"))
      (node (ref "U9") (pin "16") (pinfunction "VCC_16") (pintype "power_in"))
      (node (ref "U9") (pin "19") (pinfunction "VCC_19") (pintype "power_in"))
      (node (ref "U9") (pin "21") (pinfunction "VCC_21") (pintype "power_in"))
      (node (ref "U9") (pin "22") (pinfunction "VCC_22") (pintype "power_in"))
      (node (ref "U9") (pin "25") (pinfunction "VCC_25") (pintype "power_in"))
      (node (ref "U9") (pin "26") (pinfunction "VCC_26") (pintype "power_in"))
      (node (ref "U9") (pin "27") (pinfunction "VCC_27") (pintype "power_in"))
      (node (ref "U9") (pin "28") (pinfunction "VCC_28") (pintype "power_in"))
      (node (ref "U9") (pin "3") (pinfunction "VCC_3") (pintype "power_in"))
      (node (ref "U9") (pin "31") (pinfunction "VCC_31") (pintype "power_in"))
      (node (ref "U9") (pin "33") (pinfunction "VCC_33") (pintype "power_in"))
      (node (ref "U9") (pin "34") (pinfunction "VCC_34") (pintype "power_in"))
      (node (ref "U9") (pin "39") (pinfunction "VCC_39") (pintype "power_in"))
      (node (ref "U9") (pin "4") (pinfunction "VCC_4") (pintype "power_in"))
      (node (ref "U9") (pin "40") (pinfunction "VCC_40") (pintype "power_in"))
      (node (ref "U9") (pin "41") (pinfunction "VCC_41") (pintype "power_in"))
      (node (ref "U9") (pin "43") (pinfunction "VCC_43") (pintype "power_in"))
      (node (ref "U9") (pin "46") (pinfunction "VCC_46") (pintype "power_in"))
      (node (ref "U9") (pin "47") (pinfunction "VCC_47") (pintype "power_in"))
      (node (ref "U9") (pin "48") (pinfunction "VCC_48") (pintype "power_in"))
      (node (ref "U9") (pin "6") (pinfunction "VCC_6") (pintype "power_in"))
    )
    (net (code "65") (name "VCC3V3") (class "Default")
      (node (ref "C108") (pin "2") (pinfunction "2_2") (pintype "passive"))
      (node (ref "C111") (pin "2") (pinfunction "2_2") (pintype "passive"))
      (node (ref "C114") (pin "2") (pinfunction "2_2") (pintype "passive"))
      (node (ref "C117") (pin "2") (pinfunction "2_2") (pintype "passive"))
      (node (ref "C124") (pin "2") (pinfunction "2_2") (pintype "passive"))
      (node (ref "C125") (pin "2") (pinfunction "2_2") (pintype "passive"))
      (node (ref "C126") (pin "2") (pinfunction "2_2") (pintype "passive"))
      (node (ref "C132") (pin "1") (pinfunction "1_1") (pintype "passive"))
      (node (ref "C137") (pin "1") (pinfunction "1_1") (pintype "passive"))
      (node (ref "C142") (pin "2") (pinfunction "2_2") (pintype "passive"))
      (node (ref "C145") (pin "2") (pinfunction "2_2") (pintype "passive"))
      (node (ref "C34") (pin "2") (pinfunction "2_2") (pintype "passive"))
      (node (ref "C35") (pin "2") (pinfunction "2_2") (pintype "passive"))
      (node (ref "C36") (pin "2") (pinfunction "2_2") (pintype "passive"))
      (node (ref "C37") (pin "2") (pinfunction "2_2") (pintype "passive"))
      (node (ref "C60") (pin "2") (pinfunction "2_2") (pintype "passive"))
      (node (ref "C63") (pin "2") (pinfunction "2_2") (pintype "passive"))
      (node (ref "C66") (pin "2") (pinfunction "2_2") (pintype "passive"))
      (node (ref "C69") (pin "2") (pinfunction "2_2") (pintype "passive"))
      (node (ref "C82") (pin "2") (pinfunction "2_2") (pintype "passive"))
      (node (ref "C83") (pin "2") (pinfunction "2_2") (pintype "passive"))
      (node (ref "C84") (pin "2") (pinfunction "2_2") (pintype "passive"))
      (node (ref "C85") (pin "2") (pinfunction "2_2") (pintype "passive"))
      (node (ref "M9") (pin "2") (pinfunction "2_2") (pintype "passive"))
      (node (ref "P1") (pin "1") (pinfunction "1_1") (pintype "passive"))
      (node (ref "P1") (pin "2") (pinfunction "2_2") (pintype "passive"))
      (node (ref "R12") (pin "2") (pinfunction "2_2") (pintype "passive"))
      (node (ref "R13") (pin "2") (pinfunction "2_2") (pintype "passive"))
      (node (ref "R14") (pin "2") (pinfunction "2_2") (pintype "passive"))
      (node (ref "R15") (pin "2") (pinfunction "2_2") (pintype "passive"))
      (node (ref "R16") (pin "2") (pinfunction "2_2") (pintype "passive"))
      (node (ref "R17") (pin "2") (pinfunction "2_2") (pintype "passive"))
      (node (ref "R18") (pin "2") (pinfunction "2_2") (pintype "passive"))
      (node (ref "R19") (pin "2") (pinfunction "2_2") (pintype "passive"))
      (node (ref "R20") (pin "2") (pinfunction "2_2") (pintype "passive"))
      (node (ref "R21") (pin "2") (pinfunction "2_2") (pintype "passive"))
      (node (ref "R23") (pin "2") (pinfunction "2_2") (pintype "passive"))
      (node (ref "R24") (pin "2") (pinfunction "2_2") (pintype "passive"))
      (node (ref "U10") (pin "24") (pinfunction "VCCIO_24") (pintype "power_in"))
      (node (ref "U10") (pin "37") (pinfunction "VCCIO_37") (pintype "power_in"))
      (node (ref "U11") (pin "24") (pinfunction "VCCIO_24") (pintype "power_in"))
      (node (ref "U11") (pin "37") (pinfunction "VCCIO_37") (pintype "power_in"))
      (node (ref "U12") (pin "24") (pinfunction "VCCIO_24") (pintype "power_in"))
      (node (ref "U12") (pin "37") (pinfunction "VCCIO_37") (pintype "power_in"))
      (node (ref "U13") (pin "5") (pinfunction "VCC_5") (pintype "power_in"))
      (node (ref "U14") (pin "5") (pinfunction "VCC_5") (pintype "power_in"))
      (node (ref "U15") (pin "5") (pinfunction "VCC_5") (pintype "power_in"))
      (node (ref "U3") (pin "24") (pinfunction "VCCIO_24") (pintype "power_in"))
      (node (ref "U3") (pin "37") (pinfunction "VCCIO_37") (pintype "power_in"))
      (node (ref "U4") (pin "24") (pinfunction "VCCIO_24") (pintype "power_in"))
      (node (ref "U4") (pin "37") (pinfunction "VCCIO_37") (pintype "power_in"))
      (node (ref "U5") (pin "24") (pinfunction "VCCIO_24") (pintype "power_in"))
      (node (ref "U5") (pin "37") (pinfunction "VCCIO_37") (pintype "power_in"))
      (node (ref "U6") (pin "24") (pinfunction "VCCIO_24") (pintype "power_in"))
      (node (ref "U6") (pin "37") (pinfunction "VCCIO_37") (pintype "power_in"))
      (node (ref "U7") (pin "24") (pinfunction "VCCIO_24") (pintype "power_in"))
      (node (ref "U7") (pin "37") (pinfunction "VCCIO_37") (pintype "power_in"))
      (node (ref "U8") (pin "24") (pinfunction "VCCIO_24") (pintype "power_in"))
      (node (ref "U8") (pin "37") (pinfunction "VCCIO_37") (pintype "power_in"))
      (node (ref "U9") (pin "24") (pinfunction "VCCIO_24") (pintype "power_in"))
      (node (ref "U9") (pin "37") (pinfunction "VCCIO_37") (pintype "power_in"))
    )
    (net (code "66") (name "unconnected-(P1-Pad14)") (class "Default")
      (node (ref "P1") (pin "14") (pinfunction "14_14") (pintype "passive"))
    )
    (net (code "67") (name "unconnected-(U4-CLKOUT-Pad10)") (class "Default")
      (node (ref "U4") (pin "10") (pinfunction "CLKOUT_10") (pintype "output"))
    )
    (net (code "68") (name "unconnected-(U4-C_CLKOUT-Pad44)") (class "Default")
      (node (ref "U4") (pin "44") (pinfunction "C_CLKOUT_44") (pintype "output"))
    )
    (net (code "69") (name "unconnected-(U4-DBG0-Pad30)") (class "Default")
      (node (ref "U4") (pin "30") (pinfunction "DBG0_30") (pintype "output"))
    )
    (net (code "70") (name "unconnected-(U4-DBG1-Pad29)") (class "Default")
      (node (ref "U4") (pin "29") (pinfunction "DBG1_29") (pintype "output"))
    )
    (net (code "71") (name "unconnected-(U5-CLKOUT-Pad10)") (class "Default")
      (node (ref "U5") (pin "10") (pinfunction "CLKOUT_10") (pintype "output"))
    )
    (net (code "72") (name "unconnected-(U5-C_CLKOUT-Pad44)") (class "Default")
      (node (ref "U5") (pin "44") (pinfunction "C_CLKOUT_44") (pintype "output"))
    )
    (net (code "73") (name "unconnected-(U5-DBG0-Pad30)") (class "Default")
      (node (ref "U5") (pin "30") (pinfunction "DBG0_30") (pintype "output"))
    )
    (net (code "74") (name "unconnected-(U5-DBG1-Pad29)") (class "Default")
      (node (ref "U5") (pin "29") (pinfunction "DBG1_29") (pintype "output"))
    )
    (net (code "75") (name "unconnected-(U6-CLKOUT-Pad10)") (class "Default")
      (node (ref "U6") (pin "10") (pinfunction "CLKOUT_10") (pintype "output"))
    )
    (net (code "76") (name "unconnected-(U6-C_CLKOUT-Pad44)") (class "Default")
      (node (ref "U6") (pin "44") (pinfunction "C_CLKOUT_44") (pintype "output"))
    )
    (net (code "77") (name "unconnected-(U6-DBG0-Pad30)") (class "Default")
      (node (ref "U6") (pin "30") (pinfunction "DBG0_30") (pintype "output"))
    )
    (net (code "78") (name "unconnected-(U6-DBG1-Pad29)") (class "Default")
      (node (ref "U6") (pin "29") (pinfunction "DBG1_29") (pintype "output"))
    )
    (net (code "79") (name "unconnected-(U7-CLKOUT-Pad10)") (class "Default")
      (node (ref "U7") (pin "10") (pinfunction "CLKOUT_10") (pintype "output"))
    )
    (net (code "80") (name "unconnected-(U7-C_CLKOUT-Pad44)") (class "Default")
      (node (ref "U7") (pin "44") (pinfunction "C_CLKOUT_44") (pintype "output"))
    )
    (net (code "81") (name "unconnected-(U7-DBG0-Pad30)") (class "Default")
      (node (ref "U7") (pin "30") (pinfunction "DBG0_30") (pintype "output"))
    )
    (net (code "82") (name "unconnected-(U7-DBG1-Pad29)") (class "Default")
      (node (ref "U7") (pin "29") (pinfunction "DBG1_29") (pintype "output"))
    )
    (net (code "83") (name "unconnected-(U8-CLKOUT-Pad10)") (class "Default")
      (node (ref "U8") (pin "10") (pinfunction "CLKOUT_10") (pintype "output"))
    )
    (net (code "84") (name "unconnected-(U8-C_CLKOUT-Pad44)") (class "Default")
      (node (ref "U8") (pin "44") (pinfunction "C_CLKOUT_44") (pintype "output"))
    )
    (net (code "85") (name "unconnected-(U8-DBG0-Pad30)") (class "Default")
      (node (ref "U8") (pin "30") (pinfunction "DBG0_30") (pintype "output"))
    )
    (net (code "86") (name "unconnected-(U8-DBG1-Pad29)") (class "Default")
      (node (ref "U8") (pin "29") (pinfunction "DBG1_29") (pintype "output"))
    )
    (net (code "87") (name "unconnected-(U9-CLKOUT-Pad10)") (class "Default")
      (node (ref "U9") (pin "10") (pinfunction "CLKOUT_10") (pintype "output"))
    )
    (net (code "88") (name "unconnected-(U9-C_CLKOUT-Pad44)") (class "Default")
      (node (ref "U9") (pin "44") (pinfunction "C_CLKOUT_44") (pintype "output"))
    )
    (net (code "89") (name "unconnected-(U9-DBG0-Pad30)") (class "Default")
      (node (ref "U9") (pin "30") (pinfunction "DBG0_30") (pintype "output"))
    )
    (net (code "90") (name "unconnected-(U9-DBG1-Pad29)") (class "Default")
      (node (ref "U9") (pin "29") (pinfunction "DBG1_29") (pintype "output"))
    )
    (net (code "91") (name "unconnected-(U10-CLKOUT-Pad10)") (class "Default")
      (node (ref "U10") (pin "10") (pinfunction "CLKOUT_10") (pintype "output"))
    )
    (net (code "92") (name "unconnected-(U10-C_CLKOUT-Pad44)") (class "Default")
      (node (ref "U10") (pin "44") (pinfunction "C_CLKOUT_44") (pintype "output"))
    )
    (net (code "93") (name "unconnected-(U10-DBG0-Pad30)") (class "Default")
      (node (ref "U10") (pin "30") (pinfunction "DBG0_30") (pintype "output"))
    )
    (net (code "94") (name "unconnected-(U10-DBG1-Pad29)") (class "Default")
      (node (ref "U10") (pin "29") (pinfunction "DBG1_29") (pintype "output"))
    )
    (net (code "95") (name "unconnected-(U11-CLKOUT-Pad10)") (class "Default")
      (node (ref "U11") (pin "10") (pinfunction "CLKOUT_10") (pintype "output"))
    )
    (net (code "96") (name "unconnected-(U11-C_CLKOUT-Pad44)") (class "Default")
      (node (ref "U11") (pin "44") (pinfunction "C_CLKOUT_44") (pintype "output"))
    )
    (net (code "97") (name "unconnected-(U11-DBG0-Pad30)") (class "Default")
      (node (ref "U11") (pin "30") (pinfunction "DBG0_30") (pintype "output"))
    )
    (net (code "98") (name "unconnected-(U11-DBG1-Pad29)") (class "Default")
      (node (ref "U11") (pin "29") (pinfunction "DBG1_29") (pintype "output"))
    )
    (net (code "99") (name "unconnected-(U12-CLKOUT-Pad10)") (class "Default")
      (node (ref "U12") (pin "10") (pinfunction "CLKOUT_10") (pintype "output"))
    )
    (net (code "100") (name "unconnected-(U12-C_CLKOUT-Pad44)") (class "Default")
      (node (ref "U12") (pin "44") (pinfunction "C_CLKOUT_44") (pintype "output"))
    )
    (net (code "101") (name "unconnected-(U12-DBG0-Pad30)") (class "Default")
      (node (ref "U12") (pin "30") (pinfunction "DBG0_30") (pintype "output"))
    )
    (net (code "102") (name "unconnected-(U12-DBG1-Pad29)") (class "Default")
      (node (ref "U12") (pin "29") (pinfunction "DBG1_29") (pintype "output"))
    )
  )
)
